# LED_RGBLight_AD_2.net
KiCad netlist of a schematic drawn in Altium Designer
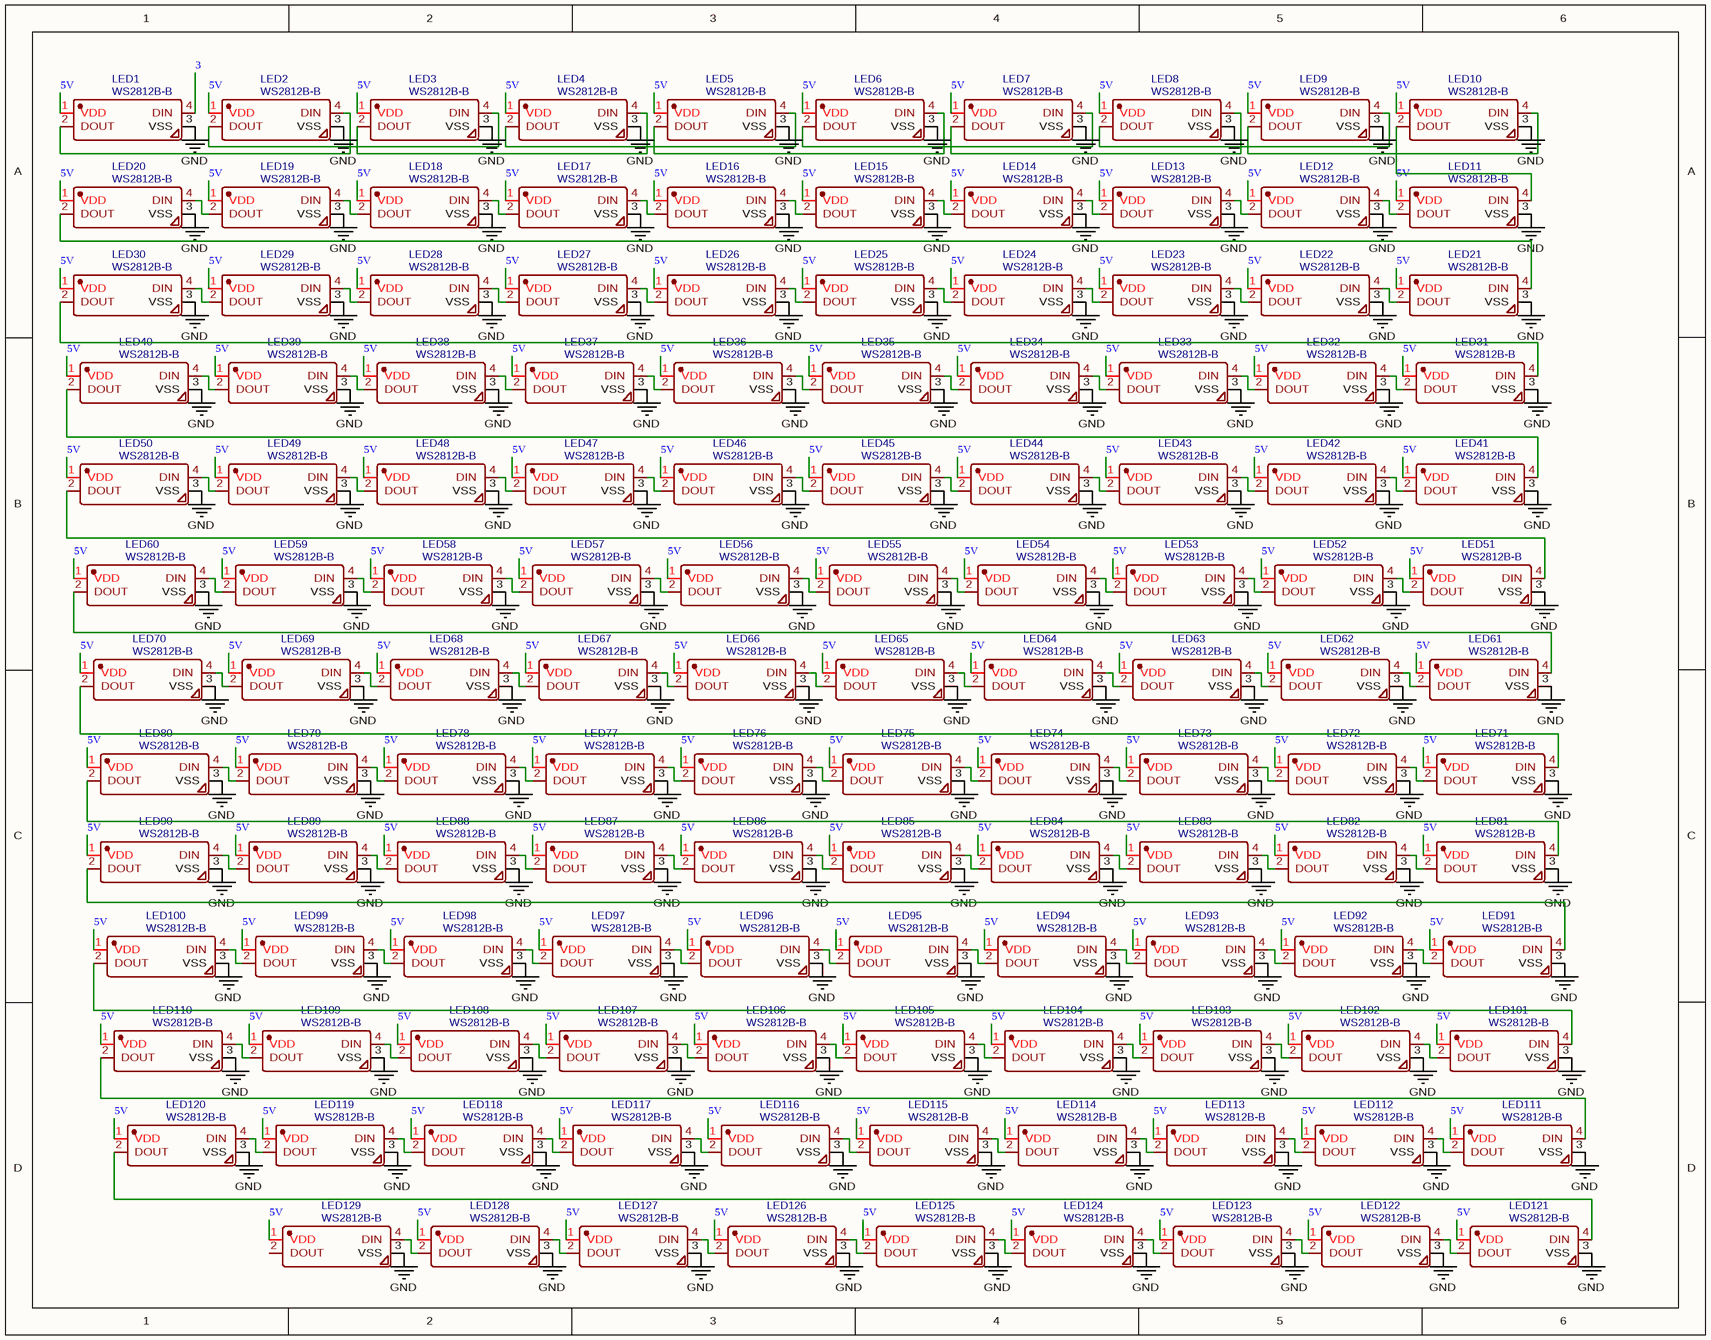
[diagram p0: LED_RGBLight_AD (2).schdoc]

(export (version "E")
  (design (tool "Eeschema 10.0.6"))
  (components
    (comp (ref "LED1")
      (value "WS2812B-B")
      (fields (field (name "BOM_SUPPLIER PART") "C114586") (field (name "CONTRIBUTOR") "LCSC"))
      (libsource (lib "altium-import") (part "root_0_WS2812B-B_"))
    )
    (comp (ref "LED2")
      (value "WS2812B-B")
      (fields (field (name "BOM_SUPPLIER PART") "C114586") (field (name "CONTRIBUTOR") "LCSC"))
      (libsource (lib "altium-import") (part "root_0_WS2812B-B_"))
    )
    (comp (ref "LED3")
      (value "WS2812B-B")
      (fields (field (name "BOM_SUPPLIER PART") "C114586") (field (name "CONTRIBUTOR") "LCSC"))
      (libsource (lib "altium-import") (part "root_0_WS2812B-B_"))
    )
    (comp (ref "LED4")
      (value "WS2812B-B")
      (fields (field (name "BOM_SUPPLIER PART") "C114586") (field (name "CONTRIBUTOR") "LCSC"))
      (libsource (lib "altium-import") (part "root_0_WS2812B-B_"))
    )
    (comp (ref "LED5")
      (value "WS2812B-B")
      (fields (field (name "BOM_SUPPLIER PART") "C114586") (field (name "CONTRIBUTOR") "LCSC"))
      (libsource (lib "altium-import") (part "root_0_WS2812B-B_"))
    )
    (comp (ref "LED6")
      (value "WS2812B-B")
      (fields (field (name "BOM_SUPPLIER PART") "C114586") (field (name "CONTRIBUTOR") "LCSC"))
      (libsource (lib "altium-import") (part "root_0_WS2812B-B_"))
    )
    (comp (ref "LED7")
      (value "WS2812B-B")
      (fields (field (name "BOM_SUPPLIER PART") "C114586") (field (name "CONTRIBUTOR") "LCSC"))
      (libsource (lib "altium-import") (part "root_0_WS2812B-B_"))
    )
    (comp (ref "LED8")
      (value "WS2812B-B")
      (fields (field (name "BOM_SUPPLIER PART") "C114586") (field (name "CONTRIBUTOR") "LCSC"))
      (libsource (lib "altium-import") (part "root_0_WS2812B-B_"))
    )
    (comp (ref "LED9")
      (value "WS2812B-B")
      (fields (field (name "BOM_SUPPLIER PART") "C114586") (field (name "CONTRIBUTOR") "LCSC"))
      (libsource (lib "altium-import") (part "root_0_WS2812B-B_"))
    )
    (comp (ref "LED10")
      (value "WS2812B-B")
      (fields (field (name "BOM_SUPPLIER PART") "C114586") (field (name "CONTRIBUTOR") "LCSC"))
      (libsource (lib "altium-import") (part "root_0_WS2812B-B_"))
    )
    (comp (ref "LED11")
      (value "WS2812B-B")
      (fields (field (name "BOM_SUPPLIER PART") "C114586") (field (name "CONTRIBUTOR") "LCSC"))
      (libsource (lib "altium-import") (part "root_0_WS2812B-B_"))
    )
    (comp (ref "LED12")
      (value "WS2812B-B")
      (fields (field (name "BOM_SUPPLIER PART") "C114586") (field (name "CONTRIBUTOR") "LCSC"))
      (libsource (lib "altium-import") (part "root_0_WS2812B-B_"))
    )
    (comp (ref "LED13")
      (value "WS2812B-B")
      (fields (field (name "BOM_SUPPLIER PART") "C114586") (field (name "CONTRIBUTOR") "LCSC"))
      (libsource (lib "altium-import") (part "root_0_WS2812B-B_"))
    )
    (comp (ref "LED14")
      (value "WS2812B-B")
      (fields (field (name "BOM_SUPPLIER PART") "C114586") (field (name "CONTRIBUTOR") "LCSC"))
      (libsource (lib "altium-import") (part "root_0_WS2812B-B_"))
    )
    (comp (ref "LED15")
      (value "WS2812B-B")
      (fields (field (name "BOM_SUPPLIER PART") "C114586") (field (name "CONTRIBUTOR") "LCSC"))
      (libsource (lib "altium-import") (part "root_0_WS2812B-B_"))
    )
    (comp (ref "LED16")
      (value "WS2812B-B")
      (fields (field (name "BOM_SUPPLIER PART") "C114586") (field (name "CONTRIBUTOR") "LCSC"))
      (libsource (lib "altium-import") (part "root_0_WS2812B-B_"))
    )
    (comp (ref "LED17")
      (value "WS2812B-B")
      (fields (field (name "BOM_SUPPLIER PART") "C114586") (field (name "CONTRIBUTOR") "LCSC"))
      (libsource (lib "altium-import") (part "root_0_WS2812B-B_"))
    )
    (comp (ref "LED18")
      (value "WS2812B-B")
      (fields (field (name "BOM_SUPPLIER PART") "C114586") (field (name "CONTRIBUTOR") "LCSC"))
      (libsource (lib "altium-import") (part "root_0_WS2812B-B_"))
    )
    (comp (ref "LED19")
      (value "WS2812B-B")
      (fields (field (name "BOM_SUPPLIER PART") "C114586") (field (name "CONTRIBUTOR") "LCSC"))
      (libsource (lib "altium-import") (part "root_0_WS2812B-B_"))
    )
    (comp (ref "LED20")
      (value "WS2812B-B")
      (fields (field (name "BOM_SUPPLIER PART") "C114586") (field (name "CONTRIBUTOR") "LCSC"))
      (libsource (lib "altium-import") (part "root_0_WS2812B-B_"))
    )
    (comp (ref "LED21")
      (value "WS2812B-B")
      (fields (field (name "BOM_SUPPLIER PART") "C114586") (field (name "CONTRIBUTOR") "LCSC"))
      (libsource (lib "altium-import") (part "root_0_WS2812B-B_"))
    )
    (comp (ref "LED22")
      (value "WS2812B-B")
      (fields (field (name "BOM_SUPPLIER PART") "C114586") (field (name "CONTRIBUTOR") "LCSC"))
      (libsource (lib "altium-import") (part "root_0_WS2812B-B_"))
    )
    (comp (ref "LED23")
      (value "WS2812B-B")
      (fields (field (name "BOM_SUPPLIER PART") "C114586") (field (name "CONTRIBUTOR") "LCSC"))
      (libsource (lib "altium-import") (part "root_0_WS2812B-B_"))
    )
    (comp (ref "LED24")
      (value "WS2812B-B")
      (fields (field (name "BOM_SUPPLIER PART") "C114586") (field (name "CONTRIBUTOR") "LCSC"))
      (libsource (lib "altium-import") (part "root_0_WS2812B-B_"))
    )
    (comp (ref "LED25")
      (value "WS2812B-B")
      (fields (field (name "BOM_SUPPLIER PART") "C114586") (field (name "CONTRIBUTOR") "LCSC"))
      (libsource (lib "altium-import") (part "root_0_WS2812B-B_"))
    )
    (comp (ref "LED26")
      (value "WS2812B-B")
      (fields (field (name "BOM_SUPPLIER PART") "C114586") (field (name "CONTRIBUTOR") "LCSC"))
      (libsource (lib "altium-import") (part "root_0_WS2812B-B_"))
    )
    (comp (ref "LED27")
      (value "WS2812B-B")
      (fields (field (name "BOM_SUPPLIER PART") "C114586") (field (name "CONTRIBUTOR") "LCSC"))
      (libsource (lib "altium-import") (part "root_0_WS2812B-B_"))
    )
    (comp (ref "LED28")
      (value "WS2812B-B")
      (fields (field (name "BOM_SUPPLIER PART") "C114586") (field (name "CONTRIBUTOR") "LCSC"))
      (libsource (lib "altium-import") (part "root_0_WS2812B-B_"))
    )
    (comp (ref "LED29")
      (value "WS2812B-B")
      (fields (field (name "BOM_SUPPLIER PART") "C114586") (field (name "CONTRIBUTOR") "LCSC"))
      (libsource (lib "altium-import") (part "root_0_WS2812B-B_"))
    )
    (comp (ref "LED30")
      (value "WS2812B-B")
      (fields (field (name "BOM_SUPPLIER PART") "C114586") (field (name "CONTRIBUTOR") "LCSC"))
      (libsource (lib "altium-import") (part "root_0_WS2812B-B_"))
    )
    (comp (ref "LED31")
      (value "WS2812B-B")
      (fields (field (name "BOM_SUPPLIER PART") "C114586") (field (name "CONTRIBUTOR") "LCSC"))
      (libsource (lib "altium-import") (part "root_0_WS2812B-B_"))
    )
    (comp (ref "LED32")
      (value "WS2812B-B")
      (fields (field (name "BOM_SUPPLIER PART") "C114586") (field (name "CONTRIBUTOR") "LCSC"))
      (libsource (lib "altium-import") (part "root_0_WS2812B-B_"))
    )
    (comp (ref "LED33")
      (value "WS2812B-B")
      (fields (field (name "BOM_SUPPLIER PART") "C114586") (field (name "CONTRIBUTOR") "LCSC"))
      (libsource (lib "altium-import") (part "root_0_WS2812B-B_"))
    )
    (comp (ref "LED34")
      (value "WS2812B-B")
      (fields (field (name "BOM_SUPPLIER PART") "C114586") (field (name "CONTRIBUTOR") "LCSC"))
      (libsource (lib "altium-import") (part "root_0_WS2812B-B_"))
    )
    (comp (ref "LED35")
      (value "WS2812B-B")
      (fields (field (name "BOM_SUPPLIER PART") "C114586") (field (name "CONTRIBUTOR") "LCSC"))
      (libsource (lib "altium-import") (part "root_0_WS2812B-B_"))
    )
    (comp (ref "LED36")
      (value "WS2812B-B")
      (fields (field (name "BOM_SUPPLIER PART") "C114586") (field (name "CONTRIBUTOR") "LCSC"))
      (libsource (lib "altium-import") (part "root_0_WS2812B-B_"))
    )
    (comp (ref "LED37")
      (value "WS2812B-B")
      (fields (field (name "BOM_SUPPLIER PART") "C114586") (field (name "CONTRIBUTOR") "LCSC"))
      (libsource (lib "altium-import") (part "root_0_WS2812B-B_"))
    )
    (comp (ref "LED38")
      (value "WS2812B-B")
      (fields (field (name "BOM_SUPPLIER PART") "C114586") (field (name "CONTRIBUTOR") "LCSC"))
      (libsource (lib "altium-import") (part "root_0_WS2812B-B_"))
    )
    (comp (ref "LED39")
      (value "WS2812B-B")
      (fields (field (name "BOM_SUPPLIER PART") "C114586") (field (name "CONTRIBUTOR") "LCSC"))
      (libsource (lib "altium-import") (part "root_0_WS2812B-B_"))
    )
    (comp (ref "LED40")
      (value "WS2812B-B")
      (fields (field (name "BOM_SUPPLIER PART") "C114586") (field (name "CONTRIBUTOR") "LCSC"))
      (libsource (lib "altium-import") (part "root_0_WS2812B-B_"))
    )
    (comp (ref "LED41")
      (value "WS2812B-B")
      (fields (field (name "BOM_SUPPLIER PART") "C114586") (field (name "CONTRIBUTOR") "LCSC"))
      (libsource (lib "altium-import") (part "root_0_WS2812B-B_"))
    )
    (comp (ref "LED42")
      (value "WS2812B-B")
      (fields (field (name "BOM_SUPPLIER PART") "C114586") (field (name "CONTRIBUTOR") "LCSC"))
      (libsource (lib "altium-import") (part "root_0_WS2812B-B_"))
    )
    (comp (ref "LED43")
      (value "WS2812B-B")
      (fields (field (name "BOM_SUPPLIER PART") "C114586") (field (name "CONTRIBUTOR") "LCSC"))
      (libsource (lib "altium-import") (part "root_0_WS2812B-B_"))
    )
    (comp (ref "LED44")
      (value "WS2812B-B")
      (fields (field (name "BOM_SUPPLIER PART") "C114586") (field (name "CONTRIBUTOR") "LCSC"))
      (libsource (lib "altium-import") (part "root_0_WS2812B-B_"))
    )
    (comp (ref "LED45")
      (value "WS2812B-B")
      (fields (field (name "BOM_SUPPLIER PART") "C114586") (field (name "CONTRIBUTOR") "LCSC"))
      (libsource (lib "altium-import") (part "root_0_WS2812B-B_"))
    )
    (comp (ref "LED46")
      (value "WS2812B-B")
      (fields (field (name "BOM_SUPPLIER PART") "C114586") (field (name "CONTRIBUTOR") "LCSC"))
      (libsource (lib "altium-import") (part "root_0_WS2812B-B_"))
    )
    (comp (ref "LED47")
      (value "WS2812B-B")
      (fields (field (name "BOM_SUPPLIER PART") "C114586") (field (name "CONTRIBUTOR") "LCSC"))
      (libsource (lib "altium-import") (part "root_0_WS2812B-B_"))
    )
    (comp (ref "LED48")
      (value "WS2812B-B")
      (fields (field (name "BOM_SUPPLIER PART") "C114586") (field (name "CONTRIBUTOR") "LCSC"))
      (libsource (lib "altium-import") (part "root_0_WS2812B-B_"))
    )
    (comp (ref "LED49")
      (value "WS2812B-B")
      (fields (field (name "BOM_SUPPLIER PART") "C114586") (field (name "CONTRIBUTOR") "LCSC"))
      (libsource (lib "altium-import") (part "root_0_WS2812B-B_"))
    )
    (comp (ref "LED50")
      (value "WS2812B-B")
      (fields (field (name "BOM_SUPPLIER PART") "C114586") (field (name "CONTRIBUTOR") "LCSC"))
      (libsource (lib "altium-import") (part "root_0_WS2812B-B_"))
    )
    (comp (ref "LED51")
      (value "WS2812B-B")
      (fields (field (name "BOM_SUPPLIER PART") "C114586") (field (name "CONTRIBUTOR") "LCSC"))
      (libsource (lib "altium-import") (part "root_0_WS2812B-B_"))
    )
    (comp (ref "LED52")
      (value "WS2812B-B")
      (fields (field (name "BOM_SUPPLIER PART") "C114586") (field (name "CONTRIBUTOR") "LCSC"))
      (libsource (lib "altium-import") (part "root_0_WS2812B-B_"))
    )
    (comp (ref "LED53")
      (value "WS2812B-B")
      (fields (field (name "BOM_SUPPLIER PART") "C114586") (field (name "CONTRIBUTOR") "LCSC"))
      (libsource (lib "altium-import") (part "root_0_WS2812B-B_"))
    )
    (comp (ref "LED54")
      (value "WS2812B-B")
      (fields (field (name "BOM_SUPPLIER PART") "C114586") (field (name "CONTRIBUTOR") "LCSC"))
      (libsource (lib "altium-import") (part "root_0_WS2812B-B_"))
    )
    (comp (ref "LED55")
      (value "WS2812B-B")
      (fields (field (name "BOM_SUPPLIER PART") "C114586") (field (name "CONTRIBUTOR") "LCSC"))
      (libsource (lib "altium-import") (part "root_0_WS2812B-B_"))
    )
    (comp (ref "LED56")
      (value "WS2812B-B")
      (fields (field (name "BOM_SUPPLIER PART") "C114586") (field (name "CONTRIBUTOR") "LCSC"))
      (libsource (lib "altium-import") (part "root_0_WS2812B-B_"))
    )
    (comp (ref "LED57")
      (value "WS2812B-B")
      (fields (field (name "BOM_SUPPLIER PART") "C114586") (field (name "CONTRIBUTOR") "LCSC"))
      (libsource (lib "altium-import") (part "root_0_WS2812B-B_"))
    )
    (comp (ref "LED58")
      (value "WS2812B-B")
      (fields (field (name "BOM_SUPPLIER PART") "C114586") (field (name "CONTRIBUTOR") "LCSC"))
      (libsource (lib "altium-import") (part "root_0_WS2812B-B_"))
    )
    (comp (ref "LED59")
      (value "WS2812B-B")
      (fields (field (name "BOM_SUPPLIER PART") "C114586") (field (name "CONTRIBUTOR") "LCSC"))
      (libsource (lib "altium-import") (part "root_0_WS2812B-B_"))
    )
    (comp (ref "LED60")
      (value "WS2812B-B")
      (fields (field (name "BOM_SUPPLIER PART") "C114586") (field (name "CONTRIBUTOR") "LCSC"))
      (libsource (lib "altium-import") (part "root_0_WS2812B-B_"))
    )
    (comp (ref "LED61")
      (value "WS2812B-B")
      (fields (field (name "BOM_SUPPLIER PART") "C114586") (field (name "CONTRIBUTOR") "LCSC"))
      (libsource (lib "altium-import") (part "root_0_WS2812B-B_"))
    )
    (comp (ref "LED62")
      (value "WS2812B-B")
      (fields (field (name "BOM_SUPPLIER PART") "C114586") (field (name "CONTRIBUTOR") "LCSC"))
      (libsource (lib "altium-import") (part "root_0_WS2812B-B_"))
    )
    (comp (ref "LED63")
      (value "WS2812B-B")
      (fields (field (name "BOM_SUPPLIER PART") "C114586") (field (name "CONTRIBUTOR") "LCSC"))
      (libsource (lib "altium-import") (part "root_0_WS2812B-B_"))
    )
    (comp (ref "LED64")
      (value "WS2812B-B")
      (fields (field (name "BOM_SUPPLIER PART") "C114586") (field (name "CONTRIBUTOR") "LCSC"))
      (libsource (lib "altium-import") (part "root_0_WS2812B-B_"))
    )
    (comp (ref "LED65")
      (value "WS2812B-B")
      (fields (field (name "BOM_SUPPLIER PART") "C114586") (field (name "CONTRIBUTOR") "LCSC"))
      (libsource (lib "altium-import") (part "root_0_WS2812B-B_"))
    )
    (comp (ref "LED66")
      (value "WS2812B-B")
      (fields (field (name "BOM_SUPPLIER PART") "C114586") (field (name "CONTRIBUTOR") "LCSC"))
      (libsource (lib "altium-import") (part "root_0_WS2812B-B_"))
    )
    (comp (ref "LED67")
      (value "WS2812B-B")
      (fields (field (name "BOM_SUPPLIER PART") "C114586") (field (name "CONTRIBUTOR") "LCSC"))
      (libsource (lib "altium-import") (part "root_0_WS2812B-B_"))
    )
    (comp (ref "LED68")
      (value "WS2812B-B")
      (fields (field (name "BOM_SUPPLIER PART") "C114586") (field (name "CONTRIBUTOR") "LCSC"))
      (libsource (lib "altium-import") (part "root_0_WS2812B-B_"))
    )
    (comp (ref "LED69")
      (value "WS2812B-B")
      (fields (field (name "BOM_SUPPLIER PART") "C114586") (field (name "CONTRIBUTOR") "LCSC"))
      (libsource (lib "altium-import") (part "root_0_WS2812B-B_"))
    )
    (comp (ref "LED70")
      (value "WS2812B-B")
      (fields (field (name "BOM_SUPPLIER PART") "C114586") (field (name "CONTRIBUTOR") "LCSC"))
      (libsource (lib "altium-import") (part "root_0_WS2812B-B_"))
    )
    (comp (ref "LED71")
      (value "WS2812B-B")
      (fields (field (name "BOM_SUPPLIER PART") "C114586") (field (name "CONTRIBUTOR") "LCSC"))
      (libsource (lib "altium-import") (part "root_0_WS2812B-B_"))
    )
    (comp (ref "LED72")
      (value "WS2812B-B")
      (fields (field (name "BOM_SUPPLIER PART") "C114586") (field (name "CONTRIBUTOR") "LCSC"))
      (libsource (lib "altium-import") (part "root_0_WS2812B-B_"))
    )
    (comp (ref "LED73")
      (value "WS2812B-B")
      (fields (field (name "BOM_SUPPLIER PART") "C114586") (field (name "CONTRIBUTOR") "LCSC"))
      (libsource (lib "altium-import") (part "root_0_WS2812B-B_"))
    )
    (comp (ref "LED74")
      (value "WS2812B-B")
      (fields (field (name "BOM_SUPPLIER PART") "C114586") (field (name "CONTRIBUTOR") "LCSC"))
      (libsource (lib "altium-import") (part "root_0_WS2812B-B_"))
    )
    (comp (ref "LED75")
      (value "WS2812B-B")
      (fields (field (name "BOM_SUPPLIER PART") "C114586") (field (name "CONTRIBUTOR") "LCSC"))
      (libsource (lib "altium-import") (part "root_0_WS2812B-B_"))
    )
    (comp (ref "LED76")
      (value "WS2812B-B")
      (fields (field (name "BOM_SUPPLIER PART") "C114586") (field (name "CONTRIBUTOR") "LCSC"))
      (libsource (lib "altium-import") (part "root_0_WS2812B-B_"))
    )
    (comp (ref "LED77")
      (value "WS2812B-B")
      (fields (field (name "BOM_SUPPLIER PART") "C114586") (field (name "CONTRIBUTOR") "LCSC"))
      (libsource (lib "altium-import") (part "root_0_WS2812B-B_"))
    )
    (comp (ref "LED78")
      (value "WS2812B-B")
      (fields (field (name "BOM_SUPPLIER PART") "C114586") (field (name "CONTRIBUTOR") "LCSC"))
      (libsource (lib "altium-import") (part "root_0_WS2812B-B_"))
    )
    (comp (ref "LED79")
      (value "WS2812B-B")
      (fields (field (name "BOM_SUPPLIER PART") "C114586") (field (name "CONTRIBUTOR") "LCSC"))
      (libsource (lib "altium-import") (part "root_0_WS2812B-B_"))
    )
    (comp (ref "LED80")
      (value "WS2812B-B")
      (fields (field (name "BOM_SUPPLIER PART") "C114586") (field (name "CONTRIBUTOR") "LCSC"))
      (libsource (lib "altium-import") (part "root_0_WS2812B-B_"))
    )
    (comp (ref "LED81")
      (value "WS2812B-B")
      (fields (field (name "BOM_SUPPLIER PART") "C114586") (field (name "CONTRIBUTOR") "LCSC"))
      (libsource (lib "altium-import") (part "root_0_WS2812B-B_"))
    )
    (comp (ref "LED82")
      (value "WS2812B-B")
      (fields (field (name "BOM_SUPPLIER PART") "C114586") (field (name "CONTRIBUTOR") "LCSC"))
      (libsource (lib "altium-import") (part "root_0_WS2812B-B_"))
    )
    (comp (ref "LED83")
      (value "WS2812B-B")
      (fields (field (name "BOM_SUPPLIER PART") "C114586") (field (name "CONTRIBUTOR") "LCSC"))
      (libsource (lib "altium-import") (part "root_0_WS2812B-B_"))
    )
    (comp (ref "LED84")
      (value "WS2812B-B")
      (fields (field (name "BOM_SUPPLIER PART") "C114586") (field (name "CONTRIBUTOR") "LCSC"))
      (libsource (lib "altium-import") (part "root_0_WS2812B-B_"))
    )
    (comp (ref "LED85")
      (value "WS2812B-B")
      (fields (field (name "BOM_SUPPLIER PART") "C114586") (field (name "CONTRIBUTOR") "LCSC"))
      (libsource (lib "altium-import") (part "root_0_WS2812B-B_"))
    )
    (comp (ref "LED86")
      (value "WS2812B-B")
      (fields (field (name "BOM_SUPPLIER PART") "C114586") (field (name "CONTRIBUTOR") "LCSC"))
      (libsource (lib "altium-import") (part "root_0_WS2812B-B_"))
    )
    (comp (ref "LED87")
      (value "WS2812B-B")
      (fields (field (name "BOM_SUPPLIER PART") "C114586") (field (name "CONTRIBUTOR") "LCSC"))
      (libsource (lib "altium-import") (part "root_0_WS2812B-B_"))
    )
    (comp (ref "LED88")
      (value "WS2812B-B")
      (fields (field (name "BOM_SUPPLIER PART") "C114586") (field (name "CONTRIBUTOR") "LCSC"))
      (libsource (lib "altium-import") (part "root_0_WS2812B-B_"))
    )
    (comp (ref "LED89")
      (value "WS2812B-B")
      (fields (field (name "BOM_SUPPLIER PART") "C114586") (field (name "CONTRIBUTOR") "LCSC"))
      (libsource (lib "altium-import") (part "root_0_WS2812B-B_"))
    )
    (comp (ref "LED90")
      (value "WS2812B-B")
      (fields (field (name "BOM_SUPPLIER PART") "C114586") (field (name "CONTRIBUTOR") "LCSC"))
      (libsource (lib "altium-import") (part "root_0_WS2812B-B_"))
    )
    (comp (ref "LED91")
      (value "WS2812B-B")
      (fields (field (name "BOM_SUPPLIER PART") "C114586") (field (name "CONTRIBUTOR") "LCSC"))
      (libsource (lib "altium-import") (part "root_0_WS2812B-B_"))
    )
    (comp (ref "LED92")
      (value "WS2812B-B")
      (fields (field (name "BOM_SUPPLIER PART") "C114586") (field (name "CONTRIBUTOR") "LCSC"))
      (libsource (lib "altium-import") (part "root_0_WS2812B-B_"))
    )
    (comp (ref "LED93")
      (value "WS2812B-B")
      (fields (field (name "BOM_SUPPLIER PART") "C114586") (field (name "CONTRIBUTOR") "LCSC"))
      (libsource (lib "altium-import") (part "root_0_WS2812B-B_"))
    )
    (comp (ref "LED94")
      (value "WS2812B-B")
      (fields (field (name "BOM_SUPPLIER PART") "C114586") (field (name "CONTRIBUTOR") "LCSC"))
      (libsource (lib "altium-import") (part "root_0_WS2812B-B_"))
    )
    (comp (ref "LED95")
      (value "WS2812B-B")
      (fields (field (name "BOM_SUPPLIER PART") "C114586") (field (name "CONTRIBUTOR") "LCSC"))
      (libsource (lib "altium-import") (part "root_0_WS2812B-B_"))
    )
    (comp (ref "LED96")
      (value "WS2812B-B")
      (fields (field (name "BOM_SUPPLIER PART") "C114586") (field (name "CONTRIBUTOR") "LCSC"))
      (libsource (lib "altium-import") (part "root_0_WS2812B-B_"))
    )
    (comp (ref "LED97")
      (value "WS2812B-B")
      (fields (field (name "BOM_SUPPLIER PART") "C114586") (field (name "CONTRIBUTOR") "LCSC"))
      (libsource (lib "altium-import") (part "root_0_WS2812B-B_"))
    )
    (comp (ref "LED98")
      (value "WS2812B-B")
      (fields (field (name "BOM_SUPPLIER PART") "C114586") (field (name "CONTRIBUTOR") "LCSC"))
      (libsource (lib "altium-import") (part "root_0_WS2812B-B_"))
    )
    (comp (ref "LED99")
      (value "WS2812B-B")
      (fields (field (name "BOM_SUPPLIER PART") "C114586") (field (name "CONTRIBUTOR") "LCSC"))
      (libsource (lib "altium-import") (part "root_0_WS2812B-B_"))
    )
    (comp (ref "LED100")
      (value "WS2812B-B")
      (fields (field (name "BOM_SUPPLIER PART") "C114586") (field (name "CONTRIBUTOR") "LCSC"))
      (libsource (lib "altium-import") (part "root_0_WS2812B-B_"))
    )
    (comp (ref "LED101")
      (value "WS2812B-B")
      (fields (field (name "BOM_SUPPLIER PART") "C114586") (field (name "CONTRIBUTOR") "LCSC"))
      (libsource (lib "altium-import") (part "root_0_WS2812B-B_"))
    )
    (comp (ref "LED102")
      (value "WS2812B-B")
      (fields (field (name "BOM_SUPPLIER PART") "C114586") (field (name "CONTRIBUTOR") "LCSC"))
      (libsource (lib "altium-import") (part "root_0_WS2812B-B_"))
    )
    (comp (ref "LED103")
      (value "WS2812B-B")
      (fields (field (name "BOM_SUPPLIER PART") "C114586") (field (name "CONTRIBUTOR") "LCSC"))
      (libsource (lib "altium-import") (part "root_0_WS2812B-B_"))
    )
    (comp (ref "LED104")
      (value "WS2812B-B")
      (fields (field (name "BOM_SUPPLIER PART") "C114586") (field (name "CONTRIBUTOR") "LCSC"))
      (libsource (lib "altium-import") (part "root_0_WS2812B-B_"))
    )
    (comp (ref "LED105")
      (value "WS2812B-B")
      (fields (field (name "BOM_SUPPLIER PART") "C114586") (field (name "CONTRIBUTOR") "LCSC"))
      (libsource (lib "altium-import") (part "root_0_WS2812B-B_"))
    )
    (comp (ref "LED106")
      (value "WS2812B-B")
      (fields (field (name "BOM_SUPPLIER PART") "C114586") (field (name "CONTRIBUTOR") "LCSC"))
      (libsource (lib "altium-import") (part "root_0_WS2812B-B_"))
    )
    (comp (ref "LED107")
      (value "WS2812B-B")
      (fields (field (name "BOM_SUPPLIER PART") "C114586") (field (name "CONTRIBUTOR") "LCSC"))
      (libsource (lib "altium-import") (part "root_0_WS2812B-B_"))
    )
    (comp (ref "LED108")
      (value "WS2812B-B")
      (fields (field (name "BOM_SUPPLIER PART") "C114586") (field (name "CONTRIBUTOR") "LCSC"))
      (libsource (lib "altium-import") (part "root_0_WS2812B-B_"))
    )
    (comp (ref "LED109")
      (value "WS2812B-B")
      (fields (field (name "BOM_SUPPLIER PART") "C114586") (field (name "CONTRIBUTOR") "LCSC"))
      (libsource (lib "altium-import") (part "root_0_WS2812B-B_"))
    )
    (comp (ref "LED110")
      (value "WS2812B-B")
      (fields (field (name "BOM_SUPPLIER PART") "C114586") (field (name "CONTRIBUTOR") "LCSC"))
      (libsource (lib "altium-import") (part "root_0_WS2812B-B_"))
    )
    (comp (ref "LED111")
      (value "WS2812B-B")
      (fields (field (name "BOM_SUPPLIER PART") "C114586") (field (name "CONTRIBUTOR") "LCSC"))
      (libsource (lib "altium-import") (part "root_0_WS2812B-B_"))
    )
    (comp (ref "LED112")
      (value "WS2812B-B")
      (fields (field (name "BOM_SUPPLIER PART") "C114586") (field (name "CONTRIBUTOR") "LCSC"))
      (libsource (lib "altium-import") (part "root_0_WS2812B-B_"))
    )
    (comp (ref "LED113")
      (value "WS2812B-B")
      (fields (field (name "BOM_SUPPLIER PART") "C114586") (field (name "CONTRIBUTOR") "LCSC"))
      (libsource (lib "altium-import") (part "root_0_WS2812B-B_"))
    )
    (comp (ref "LED114")
      (value "WS2812B-B")
      (fields (field (name "BOM_SUPPLIER PART") "C114586") (field (name "CONTRIBUTOR") "LCSC"))
      (libsource (lib "altium-import") (part "root_0_WS2812B-B_"))
    )
    (comp (ref "LED115")
      (value "WS2812B-B")
      (fields (field (name "BOM_SUPPLIER PART") "C114586") (field (name "CONTRIBUTOR") "LCSC"))
      (libsource (lib "altium-import") (part "root_0_WS2812B-B_"))
    )
    (comp (ref "LED116")
      (value "WS2812B-B")
      (fields (field (name "BOM_SUPPLIER PART") "C114586") (field (name "CONTRIBUTOR") "LCSC"))
      (libsource (lib "altium-import") (part "root_0_WS2812B-B_"))
    )
    (comp (ref "LED117")
      (value "WS2812B-B")
      (fields (field (name "BOM_SUPPLIER PART") "C114586") (field (name "CONTRIBUTOR") "LCSC"))
      (libsource (lib "altium-import") (part "root_0_WS2812B-B_"))
    )
    (comp (ref "LED118")
      (value "WS2812B-B")
      (fields (field (name "BOM_SUPPLIER PART") "C114586") (field (name "CONTRIBUTOR") "LCSC"))
      (libsource (lib "altium-import") (part "root_0_WS2812B-B_"))
    )
    (comp (ref "LED119")
      (value "WS2812B-B")
      (fields (field (name "BOM_SUPPLIER PART") "C114586") (field (name "CONTRIBUTOR") "LCSC"))
      (libsource (lib "altium-import") (part "root_0_WS2812B-B_"))
    )
    (comp (ref "LED120")
      (value "WS2812B-B")
      (fields (field (name "BOM_SUPPLIER PART") "C114586") (field (name "CONTRIBUTOR") "LCSC"))
      (libsource (lib "altium-import") (part "root_0_WS2812B-B_"))
    )
    (comp (ref "LED121")
      (value "WS2812B-B")
      (fields (field (name "BOM_SUPPLIER PART") "C114586") (field (name "CONTRIBUTOR") "LCSC"))
      (libsource (lib "altium-import") (part "root_0_WS2812B-B_"))
    )
    (comp (ref "LED122")
      (value "WS2812B-B")
      (fields (field (name "BOM_SUPPLIER PART") "C114586") (field (name "CONTRIBUTOR") "LCSC"))
      (libsource (lib "altium-import") (part "root_0_WS2812B-B_"))
    )
    (comp (ref "LED123")
      (value "WS2812B-B")
      (fields (field (name "BOM_SUPPLIER PART") "C114586") (field (name "CONTRIBUTOR") "LCSC"))
      (libsource (lib "altium-import") (part "root_0_WS2812B-B_"))
    )
    (comp (ref "LED124")
      (value "WS2812B-B")
      (fields (field (name "BOM_SUPPLIER PART") "C114586") (field (name "CONTRIBUTOR") "LCSC"))
      (libsource (lib "altium-import") (part "root_0_WS2812B-B_"))
    )
    (comp (ref "LED125")
      (value "WS2812B-B")
      (fields (field (name "BOM_SUPPLIER PART") "C114586") (field (name "CONTRIBUTOR") "LCSC"))
      (libsource (lib "altium-import") (part "root_0_WS2812B-B_"))
    )
    (comp (ref "LED126")
      (value "WS2812B-B")
      (fields (field (name "BOM_SUPPLIER PART") "C114586") (field (name "CONTRIBUTOR") "LCSC"))
      (libsource (lib "altium-import") (part "root_0_WS2812B-B_"))
    )
    (comp (ref "LED127")
      (value "WS2812B-B")
      (fields (field (name "BOM_SUPPLIER PART") "C114586") (field (name "CONTRIBUTOR") "LCSC"))
      (libsource (lib "altium-import") (part "root_0_WS2812B-B_"))
    )
    (comp (ref "LED128")
      (value "WS2812B-B")
      (fields (field (name "BOM_SUPPLIER PART") "C114586") (field (name "CONTRIBUTOR") "LCSC"))
      (libsource (lib "altium-import") (part "root_0_WS2812B-B_"))
    )
    (comp (ref "LED129")
      (value "WS2812B-B")
      (fields (field (name "BOM_SUPPLIER PART") "C114586") (field (name "CONTRIBUTOR") "LCSC"))
      (libsource (lib "altium-import") (part "root_0_WS2812B-B_"))
    )
  )
  (nets
    (net (code "1") (name "/3") (class "Default")
      (node (ref "LED1") (pin "4") (pinfunction "DIN_4") (pintype "passive"))
    )
    (net (code "2") (name "/5V") (class "Default")
      (node (ref "LED1") (pin "1") (pinfunction "VDD_1") (pintype "passive"))
      (node (ref "LED10") (pin "1") (pinfunction "VDD_1") (pintype "passive"))
      (node (ref "LED100") (pin "1") (pinfunction "VDD_1") (pintype "passive"))
      (node (ref "LED101") (pin "1") (pinfunction "VDD_1") (pintype "passive"))
      (node (ref "LED102") (pin "1") (pinfunction "VDD_1") (pintype "passive"))
      (node (ref "LED103") (pin "1") (pinfunction "VDD_1") (pintype "passive"))
      (node (ref "LED104") (pin "1") (pinfunction "VDD_1") (pintype "passive"))
      (node (ref "LED105") (pin "1") (pinfunction "VDD_1") (pintype "passive"))
      (node (ref "LED106") (pin "1") (pinfunction "VDD_1") (pintype "passive"))
      (node (ref "LED107") (pin "1") (pinfunction "VDD_1") (pintype "passive"))
      (node (ref "LED108") (pin "1") (pinfunction "VDD_1") (pintype "passive"))
      (node (ref "LED109") (pin "1") (pinfunction "VDD_1") (pintype "passive"))
      (node (ref "LED11") (pin "1") (pinfunction "VDD_1") (pintype "passive"))
      (node (ref "LED110") (pin "1") (pinfunction "VDD_1") (pintype "passive"))
      (node (ref "LED111") (pin "1") (pinfunction "VDD_1") (pintype "passive"))
      (node (ref "LED112") (pin "1") (pinfunction "VDD_1") (pintype "passive"))
      (node (ref "LED113") (pin "1") (pinfunction "VDD_1") (pintype "passive"))
      (node (ref "LED114") (pin "1") (pinfunction "VDD_1") (pintype "passive"))
      (node (ref "LED115") (pin "1") (pinfunction "VDD_1") (pintype "passive"))
      (node (ref "LED116") (pin "1") (pinfunction "VDD_1") (pintype "passive"))
      (node (ref "LED117") (pin "1") (pinfunction "VDD_1") (pintype "passive"))
      (node (ref "LED118") (pin "1") (pinfunction "VDD_1") (pintype "passive"))
      (node (ref "LED119") (pin "1") (pinfunction "VDD_1") (pintype "passive"))
      (node (ref "LED12") (pin "1") (pinfunction "VDD_1") (pintype "passive"))
      (node (ref "LED120") (pin "1") (pinfunction "VDD_1") (pintype "passive"))
      (node (ref "LED121") (pin "1") (pinfunction "VDD_1") (pintype "passive"))
      (node (ref "LED122") (pin "1") (pinfunction "VDD_1") (pintype "passive"))
      (node (ref "LED123") (pin "1") (pinfunction "VDD_1") (pintype "passive"))
      (node (ref "LED124") (pin "1") (pinfunction "VDD_1") (pintype "passive"))
      (node (ref "LED125") (pin "1") (pinfunction "VDD_1") (pintype "passive"))
      (node (ref "LED126") (pin "1") (pinfunction "VDD_1") (pintype "passive"))
      (node (ref "LED127") (pin "1") (pinfunction "VDD_1") (pintype "passive"))
      (node (ref "LED128") (pin "1") (pinfunction "VDD_1") (pintype "passive"))
      (node (ref "LED129") (pin "1") (pinfunction "VDD_1") (pintype "passive"))
      (node (ref "LED13") (pin "1") (pinfunction "VDD_1") (pintype "passive"))
      (node (ref "LED14") (pin "1") (pinfunction "VDD_1") (pintype "passive"))
      (node (ref "LED15") (pin "1") (pinfunction "VDD_1") (pintype "passive"))
      (node (ref "LED16") (pin "1") (pinfunction "VDD_1") (pintype "passive"))
      (node (ref "LED17") (pin "1") (pinfunction "VDD_1") (pintype "passive"))
      (node (ref "LED18") (pin "1") (pinfunction "VDD_1") (pintype "passive"))
      (node (ref "LED19") (pin "1") (pinfunction "VDD_1") (pintype "passive"))
      (node (ref "LED2") (pin "1") (pinfunction "VDD_1") (pintype "passive"))
      (node (ref "LED20") (pin "1") (pinfunction "VDD_1") (pintype "passive"))
      (node (ref "LED21") (pin "1") (pinfunction "VDD_1") (pintype "passive"))
      (node (ref "LED22") (pin "1") (pinfunction "VDD_1") (pintype "passive"))
      (node (ref "LED23") (pin "1") (pinfunction "VDD_1") (pintype "passive"))
      (node (ref "LED24") (pin "1") (pinfunction "VDD_1") (pintype "passive"))
      (node (ref "LED25") (pin "1") (pinfunction "VDD_1") (pintype "passive"))
      (node (ref "LED26") (pin "1") (pinfunction "VDD_1") (pintype "passive"))
      (node (ref "LED27") (pin "1") (pinfunction "VDD_1") (pintype "passive"))
      (node (ref "LED28") (pin "1") (pinfunction "VDD_1") (pintype "passive"))
      (node (ref "LED29") (pin "1") (pinfunction "VDD_1") (pintype "passive"))
      (node (ref "LED3") (pin "1") (pinfunction "VDD_1") (pintype "passive"))
      (node (ref "LED30") (pin "1") (pinfunction "VDD_1") (pintype "passive"))
      (node (ref "LED31") (pin "1") (pinfunction "VDD_1") (pintype "passive"))
      (node (ref "LED32") (pin "1") (pinfunction "VDD_1") (pintype "passive"))
      (node (ref "LED33") (pin "1") (pinfunction "VDD_1") (pintype "passive"))
      (node (ref "LED34") (pin "1") (pinfunction "VDD_1") (pintype "passive"))
      (node (ref "LED35") (pin "1") (pinfunction "VDD_1") (pintype "passive"))
      (node (ref "LED36") (pin "1") (pinfunction "VDD_1") (pintype "passive"))
      (node (ref "LED37") (pin "1") (pinfunction "VDD_1") (pintype "passive"))
      (node (ref "LED38") (pin "1") (pinfunction "VDD_1") (pintype "passive"))
      (node (ref "LED39") (pin "1") (pinfunction "VDD_1") (pintype "passive"))
      (node (ref "LED4") (pin "1") (pinfunction "VDD_1") (pintype "passive"))
      (node (ref "LED40") (pin "1") (pinfunction "VDD_1") (pintype "passive"))
      (node (ref "LED41") (pin "1") (pinfunction "VDD_1") (pintype "passive"))
      (node (ref "LED42") (pin "1") (pinfunction "VDD_1") (pintype "passive"))
      (node (ref "LED43") (pin "1") (pinfunction "VDD_1") (pintype "passive"))
      (node (ref "LED44") (pin "1") (pinfunction "VDD_1") (pintype "passive"))
      (node (ref "LED45") (pin "1") (pinfunction "VDD_1") (pintype "passive"))
      (node (ref "LED46") (pin "1") (pinfunction "VDD_1") (pintype "passive"))
      (node (ref "LED47") (pin "1") (pinfunction "VDD_1") (pintype "passive"))
      (node (ref "LED48") (pin "1") (pinfunction "VDD_1") (pintype "passive"))
      (node (ref "LED49") (pin "1") (pinfunction "VDD_1") (pintype "passive"))
      (node (ref "LED5") (pin "1") (pinfunction "VDD_1") (pintype "passive"))
      (node (ref "LED50") (pin "1") (pinfunction "VDD_1") (pintype "passive"))
      (node (ref "LED51") (pin "1") (pinfunction "VDD_1") (pintype "passive"))
      (node (ref "LED52") (pin "1") (pinfunction "VDD_1") (pintype "passive"))
      (node (ref "LED53") (pin "1") (pinfunction "VDD_1") (pintype "passive"))
      (node (ref "LED54") (pin "1") (pinfunction "VDD_1") (pintype "passive"))
      (node (ref "LED55") (pin "1") (pinfunction "VDD_1") (pintype "passive"))
      (node (ref "LED56") (pin "1") (pinfunction "VDD_1") (pintype "passive"))
      (node (ref "LED57") (pin "1") (pinfunction "VDD_1") (pintype "passive"))
      (node (ref "LED58") (pin "1") (pinfunction "VDD_1") (pintype "passive"))
      (node (ref "LED59") (pin "1") (pinfunction "VDD_1") (pintype "passive"))
      (node (ref "LED6") (pin "1") (pinfunction "VDD_1") (pintype "passive"))
      (node (ref "LED60") (pin "1") (pinfunction "VDD_1") (pintype "passive"))
      (node (ref "LED61") (pin "1") (pinfunction "VDD_1") (pintype "passive"))
      (node (ref "LED62") (pin "1") (pinfunction "VDD_1") (pintype "passive"))
      (node (ref "LED63") (pin "1") (pinfunction "VDD_1") (pintype "passive"))
      (node (ref "LED64") (pin "1") (pinfunction "VDD_1") (pintype "passive"))
      (node (ref "LED65") (pin "1") (pinfunction "VDD_1") (pintype "passive"))
      (node (ref "LED66") (pin "1") (pinfunction "VDD_1") (pintype "passive"))
      (node (ref "LED67") (pin "1") (pinfunction "VDD_1") (pintype "passive"))
      (node (ref "LED68") (pin "1") (pinfunction "VDD_1") (pintype "passive"))
      (node (ref "LED69") (pin "1") (pinfunction "VDD_1") (pintype "passive"))
      (node (ref "LED7") (pin "1") (pinfunction "VDD_1") (pintype "passive"))
      (node (ref "LED70") (pin "1") (pinfunction "VDD_1") (pintype "passive"))
      (node (ref "LED71") (pin "1") (pinfunction "VDD_1") (pintype "passive"))
      (node (ref "LED72") (pin "1") (pinfunction "VDD_1") (pintype "passive"))
      (node (ref "LED73") (pin "1") (pinfunction "VDD_1") (pintype "passive"))
      (node (ref "LED74") (pin "1") (pinfunction "VDD_1") (pintype "passive"))
      (node (ref "LED75") (pin "1") (pinfunction "VDD_1") (pintype "passive"))
      (node (ref "LED76") (pin "1") (pinfunction "VDD_1") (pintype "passive"))
      (node (ref "LED77") (pin "1") (pinfunction "VDD_1") (pintype "passive"))
      (node (ref "LED78") (pin "1") (pinfunction "VDD_1") (pintype "passive"))
      (node (ref "LED79") (pin "1") (pinfunction "VDD_1") (pintype "passive"))
      (node (ref "LED8") (pin "1") (pinfunction "VDD_1") (pintype "passive"))
      (node (ref "LED80") (pin "1") (pinfunction "VDD_1") (pintype "passive"))
      (node (ref "LED81") (pin "1") (pinfunction "VDD_1") (pintype "passive"))
      (node (ref "LED82") (pin "1") (pinfunction "VDD_1") (pintype "passive"))
      (node (ref "LED83") (pin "1") (pinfunction "VDD_1") (pintype "passive"))
      (node (ref "LED84") (pin "1") (pinfunction "VDD_1") (pintype "passive"))
      (node (ref "LED85") (pin "1") (pinfunction "VDD_1") (pintype "passive"))
      (node (ref "LED86") (pin "1") (pinfunction "VDD_1") (pintype "passive"))
      (node (ref "LED87") (pin "1") (pinfunction "VDD_1") (pintype "passive"))
      (node (ref "LED88") (pin "1") (pinfunction "VDD_1") (pintype "passive"))
      (node (ref "LED89") (pin "1") (pinfunction "VDD_1") (pintype "passive"))
      (node (ref "LED9") (pin "1") (pinfunction "VDD_1") (pintype "passive"))
      (node (ref "LED90") (pin "1") (pinfunction "VDD_1") (pintype "passive"))
      (node (ref "LED91") (pin "1") (pinfunction "VDD_1") (pintype "passive"))
      (node (ref "LED92") (pin "1") (pinfunction "VDD_1") (pintype "passive"))
      (node (ref "LED93") (pin "1") (pinfunction "VDD_1") (pintype "passive"))
      (node (ref "LED94") (pin "1") (pinfunction "VDD_1") (pintype "passive"))
      (node (ref "LED95") (pin "1") (pinfunction "VDD_1") (pintype "passive"))
      (node (ref "LED96") (pin "1") (pinfunction "VDD_1") (pintype "passive"))
      (node (ref "LED97") (pin "1") (pinfunction "VDD_1") (pintype "passive"))
      (node (ref "LED98") (pin "1") (pinfunction "VDD_1") (pintype "passive"))
      (node (ref "LED99") (pin "1") (pinfunction "VDD_1") (pintype "passive"))
    )
    (net (code "3") (name "GND") (class "Default")
      (node (ref "LED1") (pin "3") (pinfunction "VSS_3") (pintype "passive"))
      (node (ref "LED10") (pin "3") (pinfunction "VSS_3") (pintype "passive"))
      (node (ref "LED100") (pin "3") (pinfunction "VSS_3") (pintype "passive"))
      (node (ref "LED101") (pin "3") (pinfunction "VSS_3") (pintype "passive"))
      (node (ref "LED102") (pin "3") (pinfunction "VSS_3") (pintype "passive"))
      (node (ref "LED103") (pin "3") (pinfunction "VSS_3") (pintype "passive"))
      (node (ref "LED104") (pin "3") (pinfunction "VSS_3") (pintype "passive"))
      (node (ref "LED105") (pin "3") (pinfunction "VSS_3") (pintype "passive"))
      (node (ref "LED106") (pin "3") (pinfunction "VSS_3") (pintype "passive"))
      (node (ref "LED107") (pin "3") (pinfunction "VSS_3") (pintype "passive"))
      (node (ref "LED108") (pin "3") (pinfunction "VSS_3") (pintype "passive"))
      (node (ref "LED109") (pin "3") (pinfunction "VSS_3") (pintype "passive"))
      (node (ref "LED11") (pin "3") (pinfunction "VSS_3") (pintype "passive"))
      (node (ref "LED110") (pin "3") (pinfunction "VSS_3") (pintype "passive"))
      (node (ref "LED111") (pin "3") (pinfunction "VSS_3") (pintype "passive"))
      (node (ref "LED112") (pin "3") (pinfunction "VSS_3") (pintype "passive"))
      (node (ref "LED113") (pin "3") (pinfunction "VSS_3") (pintype "passive"))
      (node (ref "LED114") (pin "3") (pinfunction "VSS_3") (pintype "passive"))
      (node (ref "LED115") (pin "3") (pinfunction "VSS_3") (pintype "passive"))
      (node (ref "LED116") (pin "3") (pinfunction "VSS_3") (pintype "passive"))
      (node (ref "LED117") (pin "3") (pinfunction "VSS_3") (pintype "passive"))
      (node (ref "LED118") (pin "3") (pinfunction "VSS_3") (pintype "passive"))
      (node (ref "LED119") (pin "3") (pinfunction "VSS_3") (pintype "passive"))
      (node (ref "LED12") (pin "3") (pinfunction "VSS_3") (pintype "passive"))
      (node (ref "LED120") (pin "3") (pinfunction "VSS_3") (pintype "passive"))
      (node (ref "LED121") (pin "3") (pinfunction "VSS_3") (pintype "passive"))
      (node (ref "LED122") (pin "3") (pinfunction "VSS_3") (pintype "passive"))
      (node (ref "LED123") (pin "3") (pinfunction "VSS_3") (pintype "passive"))
      (node (ref "LED124") (pin "3") (pinfunction "VSS_3") (pintype "passive"))
      (node (ref "LED125") (pin "3") (pinfunction "VSS_3") (pintype "passive"))
      (node (ref "LED126") (pin "3") (pinfunction "VSS_3") (pintype "passive"))
      (node (ref "LED127") (pin "3") (pinfunction "VSS_3") (pintype "passive"))
      (node (ref "LED128") (pin "3") (pinfunction "VSS_3") (pintype "passive"))
      (node (ref "LED129") (pin "3") (pinfunction "VSS_3") (pintype "passive"))
      (node (ref "LED13") (pin "3") (pinfunction "VSS_3") (pintype "passive"))
      (node (ref "LED14") (pin "3") (pinfunction "VSS_3") (pintype "passive"))
      (node (ref "LED15") (pin "3") (pinfunction "VSS_3") (pintype "passive"))
      (node (ref "LED16") (pin "3") (pinfunction "VSS_3") (pintype "passive"))
      (node (ref "LED17") (pin "3") (pinfunction "VSS_3") (pintype "passive"))
      (node (ref "LED18") (pin "3") (pinfunction "VSS_3") (pintype "passive"))
      (node (ref "LED19") (pin "3") (pinfunction "VSS_3") (pintype "passive"))
      (node (ref "LED2") (pin "3") (pinfunction "VSS_3") (pintype "passive"))
      (node (ref "LED20") (pin "3") (pinfunction "VSS_3") (pintype "passive"))
      (node (ref "LED21") (pin "3") (pinfunction "VSS_3") (pintype "passive"))
      (node (ref "LED22") (pin "3") (pinfunction "VSS_3") (pintype "passive"))
      (node (ref "LED23") (pin "3") (pinfunction "VSS_3") (pintype "passive"))
      (node (ref "LED24") (pin "3") (pinfunction "VSS_3") (pintype "passive"))
      (node (ref "LED25") (pin "3") (pinfunction "VSS_3") (pintype "passive"))
      (node (ref "LED26") (pin "3") (pinfunction "VSS_3") (pintype "passive"))
      (node (ref "LED27") (pin "3") (pinfunction "VSS_3") (pintype "passive"))
      (node (ref "LED28") (pin "3") (pinfunction "VSS_3") (pintype "passive"))
      (node (ref "LED29") (pin "3") (pinfunction "VSS_3") (pintype "passive"))
      (node (ref "LED3") (pin "3") (pinfunction "VSS_3") (pintype "passive"))
      (node (ref "LED30") (pin "3") (pinfunction "VSS_3") (pintype "passive"))
      (node (ref "LED31") (pin "3") (pinfunction "VSS_3") (pintype "passive"))
      (node (ref "LED32") (pin "3") (pinfunction "VSS_3") (pintype "passive"))
      (node (ref "LED33") (pin "3") (pinfunction "VSS_3") (pintype "passive"))
      (node (ref "LED34") (pin "3") (pinfunction "VSS_3") (pintype "passive"))
      (node (ref "LED35") (pin "3") (pinfunction "VSS_3") (pintype "passive"))
      (node (ref "LED36") (pin "3") (pinfunction "VSS_3") (pintype "passive"))
      (node (ref "LED37") (pin "3") (pinfunction "VSS_3") (pintype "passive"))
      (node (ref "LED38") (pin "3") (pinfunction "VSS_3") (pintype "passive"))
      (node (ref "LED39") (pin "3") (pinfunction "VSS_3") (pintype "passive"))
      (node (ref "LED4") (pin "3") (pinfunction "VSS_3") (pintype "passive"))
      (node (ref "LED40") (pin "3") (pinfunction "VSS_3") (pintype "passive"))
      (node (ref "LED41") (pin "3") (pinfunction "VSS_3") (pintype "passive"))
      (node (ref "LED42") (pin "3") (pinfunction "VSS_3") (pintype "passive"))
      (node (ref "LED43") (pin "3") (pinfunction "VSS_3") (pintype "passive"))
      (node (ref "LED44") (pin "3") (pinfunction "VSS_3") (pintype "passive"))
      (node (ref "LED45") (pin "3") (pinfunction "VSS_3") (pintype "passive"))
      (node (ref "LED46") (pin "3") (pinfunction "VSS_3") (pintype "passive"))
      (node (ref "LED47") (pin "3") (pinfunction "VSS_3") (pintype "passive"))
      (node (ref "LED48") (pin "3") (pinfunction "VSS_3") (pintype "passive"))
      (node (ref "LED49") (pin "3") (pinfunction "VSS_3") (pintype "passive"))
      (node (ref "LED5") (pin "3") (pinfunction "VSS_3") (pintype "passive"))
      (node (ref "LED50") (pin "3") (pinfunction "VSS_3") (pintype "passive"))
      (node (ref "LED51") (pin "3") (pinfunction "VSS_3") (pintype "passive"))
      (node (ref "LED52") (pin "3") (pinfunction "VSS_3") (pintype "passive"))
      (node (ref "LED53") (pin "3") (pinfunction "VSS_3") (pintype "passive"))
      (node (ref "LED54") (pin "3") (pinfunction "VSS_3") (pintype "passive"))
      (node (ref "LED55") (pin "3") (pinfunction "VSS_3") (pintype "passive"))
      (node (ref "LED56") (pin "3") (pinfunction "VSS_3") (pintype "passive"))
      (node (ref "LED57") (pin "3") (pinfunction "VSS_3") (pintype "passive"))
      (node (ref "LED58") (pin "3") (pinfunction "VSS_3") (pintype "passive"))
      (node (ref "LED59") (pin "3") (pinfunction "VSS_3") (pintype "passive"))
      (node (ref "LED6") (pin "3") (pinfunction "VSS_3") (pintype "passive"))
      (node (ref "LED60") (pin "3") (pinfunction "VSS_3") (pintype "passive"))
      (node (ref "LED61") (pin "3") (pinfunction "VSS_3") (pintype "passive"))
      (node (ref "LED62") (pin "3") (pinfunction "VSS_3") (pintype "passive"))
      (node (ref "LED63") (pin "3") (pinfunction "VSS_3") (pintype "passive"))
      (node (ref "LED64") (pin "3") (pinfunction "VSS_3") (pintype "passive"))
      (node (ref "LED65") (pin "3") (pinfunction "VSS_3") (pintype "passive"))
      (node (ref "LED66") (pin "3") (pinfunction "VSS_3") (pintype "passive"))
      (node (ref "LED67") (pin "3") (pinfunction "VSS_3") (pintype "passive"))
      (node (ref "LED68") (pin "3") (pinfunction "VSS_3") (pintype "passive"))
      (node (ref "LED69") (pin "3") (pinfunction "VSS_3") (pintype "passive"))
      (node (ref "LED7") (pin "3") (pinfunction "VSS_3") (pintype "passive"))
      (node (ref "LED70") (pin "3") (pinfunction "VSS_3") (pintype "passive"))
      (node (ref "LED71") (pin "3") (pinfunction "VSS_3") (pintype "passive"))
      (node (ref "LED72") (pin "3") (pinfunction "VSS_3") (pintype "passive"))
      (node (ref "LED73") (pin "3") (pinfunction "VSS_3") (pintype "passive"))
      (node (ref "LED74") (pin "3") (pinfunction "VSS_3") (pintype "passive"))
      (node (ref "LED75") (pin "3") (pinfunction "VSS_3") (pintype "passive"))
      (node (ref "LED76") (pin "3") (pinfunction "VSS_3") (pintype "passive"))
      (node (ref "LED77") (pin "3") (pinfunction "VSS_3") (pintype "passive"))
      (node (ref "LED78") (pin "3") (pinfunction "VSS_3") (pintype "passive"))
      (node (ref "LED79") (pin "3") (pinfunction "VSS_3") (pintype "passive"))
      (node (ref "LED8") (pin "3") (pinfunction "VSS_3") (pintype "passive"))
      (node (ref "LED80") (pin "3") (pinfunction "VSS_3") (pintype "passive"))
      (node (ref "LED81") (pin "3") (pinfunction "VSS_3") (pintype "passive"))
      (node (ref "LED82") (pin "3") (pinfunction "VSS_3") (pintype "passive"))
      (node (ref "LED83") (pin "3") (pinfunction "VSS_3") (pintype "passive"))
      (node (ref "LED84") (pin "3") (pinfunction "VSS_3") (pintype "passive"))
      (node (ref "LED85") (pin "3") (pinfunction "VSS_3") (pintype "passive"))
      (node (ref "LED86") (pin "3") (pinfunction "VSS_3") (pintype "passive"))
      (node (ref "LED87") (pin "3") (pinfunction "VSS_3") (pintype "passive"))
      (node (ref "LED88") (pin "3") (pinfunction "VSS_3") (pintype "passive"))
      (node (ref "LED89") (pin "3") (pinfunction "VSS_3") (pintype "passive"))
      (node (ref "LED9") (pin "3") (pinfunction "VSS_3") (pintype "passive"))
      (node (ref "LED90") (pin "3") (pinfunction "VSS_3") (pintype "passive"))
      (node (ref "LED91") (pin "3") (pinfunction "VSS_3") (pintype "passive"))
      (node (ref "LED92") (pin "3") (pinfunction "VSS_3") (pintype "passive"))
      (node (ref "LED93") (pin "3") (pinfunction "VSS_3") (pintype "passive"))
      (node (ref "LED94") (pin "3") (pinfunction "VSS_3") (pintype "passive"))
      (node (ref "LED95") (pin "3") (pinfunction "VSS_3") (pintype "passive"))
      (node (ref "LED96") (pin "3") (pinfunction "VSS_3") (pintype "passive"))
      (node (ref "LED97") (pin "3") (pinfunction "VSS_3") (pintype "passive"))
      (node (ref "LED98") (pin "3") (pinfunction "VSS_3") (pintype "passive"))
      (node (ref "LED99") (pin "3") (pinfunction "VSS_3") (pintype "passive"))
    )
    (net (code "4") (name "Net-(LED1-DOUT)") (class "Default")
      (node (ref "LED1") (pin "2") (pinfunction "DOUT_2") (pintype "passive"))
      (node (ref "LED2") (pin "4") (pinfunction "DIN_4") (pintype "passive"))
    )
    (net (code "5") (name "Net-(LED2-DOUT)") (class "Default")
      (node (ref "LED2") (pin "2") (pinfunction "DOUT_2") (pintype "passive"))
      (node (ref "LED3") (pin "4") (pinfunction "DIN_4") (pintype "passive"))
    )
    (net (code "6") (name "Net-(LED3-DOUT)") (class "Default")
      (node (ref "LED3") (pin "2") (pinfunction "DOUT_2") (pintype "passive"))
      (node (ref "LED4") (pin "4") (pinfunction "DIN_4") (pintype "passive"))
    )
    (net (code "7") (name "Net-(LED4-DOUT)") (class "Default")
      (node (ref "LED4") (pin "2") (pinfunction "DOUT_2") (pintype "passive"))
      (node (ref "LED5") (pin "4") (pinfunction "DIN_4") (pintype "passive"))
    )
    (net (code "8") (name "Net-(LED5-DOUT)") (class "Default")
      (node (ref "LED5") (pin "2") (pinfunction "DOUT_2") (pintype "passive"))
      (node (ref "LED6") (pin "4") (pinfunction "DIN_4") (pintype "passive"))
    )
    (net (code "9") (name "Net-(LED6-DOUT)") (class "Default")
      (node (ref "LED6") (pin "2") (pinfunction "DOUT_2") (pintype "passive"))
      (node (ref "LED7") (pin "4") (pinfunction "DIN_4") (pintype "passive"))
    )
    (net (code "10") (name "Net-(LED7-DOUT)") (class "Default")
      (node (ref "LED7") (pin "2") (pinfunction "DOUT_2") (pintype "passive"))
      (node (ref "LED8") (pin "4") (pinfunction "DIN_4") (pintype "passive"))
    )
    (net (code "11") (name "Net-(LED8-DOUT)") (class "Default")
      (node (ref "LED8") (pin "2") (pinfunction "DOUT_2") (pintype "passive"))
      (node (ref "LED9") (pin "4") (pinfunction "DIN_4") (pintype "passive"))
    )
    (net (code "12") (name "Net-(LED10-DIN)") (class "Default")
      (node (ref "LED10") (pin "4") (pinfunction "DIN_4") (pintype "passive"))
      (node (ref "LED9") (pin "2") (pinfunction "DOUT_2") (pintype "passive"))
    )
    (net (code "13") (name "Net-(LED10-DOUT)") (class "Default")
      (node (ref "LED10") (pin "2") (pinfunction "DOUT_2") (pintype "passive"))
      (node (ref "LED11") (pin "4") (pinfunction "DIN_4") (pintype "passive"))
    )
    (net (code "14") (name "Net-(LED11-DOUT)") (class "Default")
      (node (ref "LED11") (pin "2") (pinfunction "DOUT_2") (pintype "passive"))
      (node (ref "LED12") (pin "4") (pinfunction "DIN_4") (pintype "passive"))
    )
    (net (code "15") (name "Net-(LED12-DOUT)") (class "Default")
      (node (ref "LED12") (pin "2") (pinfunction "DOUT_2") (pintype "passive"))
      (node (ref "LED13") (pin "4") (pinfunction "DIN_4") (pintype "passive"))
    )
    (net (code "16") (name "Net-(LED13-DOUT)") (class "Default")
      (node (ref "LED13") (pin "2") (pinfunction "DOUT_2") (pintype "passive"))
      (node (ref "LED14") (pin "4") (pinfunction "DIN_4") (pintype "passive"))
    )
    (net (code "17") (name "Net-(LED14-DOUT)") (class "Default")
      (node (ref "LED14") (pin "2") (pinfunction "DOUT_2") (pintype "passive"))
      (node (ref "LED15") (pin "4") (pinfunction "DIN_4") (pintype "passive"))
    )
    (net (code "18") (name "Net-(LED15-DOUT)") (class "Default")
      (node (ref "LED15") (pin "2") (pinfunction "DOUT_2") (pintype "passive"))
      (node (ref "LED16") (pin "4") (pinfunction "DIN_4") (pintype "passive"))
    )
    (net (code "19") (name "Net-(LED16-DOUT)") (class "Default")
      (node (ref "LED16") (pin "2") (pinfunction "DOUT_2") (pintype "passive"))
      (node (ref "LED17") (pin "4") (pinfunction "DIN_4") (pintype "passive"))
    )
    (net (code "20") (name "Net-(LED17-DOUT)") (class "Default")
      (node (ref "LED17") (pin "2") (pinfunction "DOUT_2") (pintype "passive"))
      (node (ref "LED18") (pin "4") (pinfunction "DIN_4") (pintype "passive"))
    )
    (net (code "21") (name "Net-(LED18-DOUT)") (class "Default")
      (node (ref "LED18") (pin "2") (pinfunction "DOUT_2") (pintype "passive"))
      (node (ref "LED19") (pin "4") (pinfunction "DIN_4") (pintype "passive"))
    )
    (net (code "22") (name "Net-(LED19-DOUT)") (class "Default")
      (node (ref "LED19") (pin "2") (pinfunction "DOUT_2") (pintype "passive"))
      (node (ref "LED20") (pin "4") (pinfunction "DIN_4") (pintype "passive"))
    )
    (net (code "23") (name "Net-(LED20-DOUT)") (class "Default")
      (node (ref "LED20") (pin "2") (pinfunction "DOUT_2") (pintype "passive"))
      (node (ref "LED21") (pin "4") (pinfunction "DIN_4") (pintype "passive"))
    )
    (net (code "24") (name "Net-(LED21-DOUT)") (class "Default")
      (node (ref "LED21") (pin "2") (pinfunction "DOUT_2") (pintype "passive"))
      (node (ref "LED22") (pin "4") (pinfunction "DIN_4") (pintype "passive"))
    )
    (net (code "25") (name "Net-(LED22-DOUT)") (class "Default")
      (node (ref "LED22") (pin "2") (pinfunction "DOUT_2") (pintype "passive"))
      (node (ref "LED23") (pin "4") (pinfunction "DIN_4") (pintype "passive"))
    )
    (net (code "26") (name "Net-(LED23-DOUT)") (class "Default")
      (node (ref "LED23") (pin "2") (pinfunction "DOUT_2") (pintype "passive"))
      (node (ref "LED24") (pin "4") (pinfunction "DIN_4") (pintype "passive"))
    )
    (net (code "27") (name "Net-(LED24-DOUT)") (class "Default")
      (node (ref "LED24") (pin "2") (pinfunction "DOUT_2") (pintype "passive"))
      (node (ref "LED25") (pin "4") (pinfunction "DIN_4") (pintype "passive"))
    )
    (net (code "28") (name "Net-(LED25-DOUT)") (class "Default")
      (node (ref "LED25") (pin "2") (pinfunction "DOUT_2") (pintype "passive"))
      (node (ref "LED26") (pin "4") (pinfunction "DIN_4") (pintype "passive"))
    )
    (net (code "29") (name "Net-(LED26-DOUT)") (class "Default")
      (node (ref "LED26") (pin "2") (pinfunction "DOUT_2") (pintype "passive"))
      (node (ref "LED27") (pin "4") (pinfunction "DIN_4") (pintype "passive"))
    )
    (net (code "30") (name "Net-(LED27-DOUT)") (class "Default")
      (node (ref "LED27") (pin "2") (pinfunction "DOUT_2") (pintype "passive"))
      (node (ref "LED28") (pin "4") (pinfunction "DIN_4") (pintype "passive"))
    )
    (net (code "31") (name "Net-(LED28-DOUT)") (class "Default")
      (node (ref "LED28") (pin "2") (pinfunction "DOUT_2") (pintype "passive"))
      (node (ref "LED29") (pin "4") (pinfunction "DIN_4") (pintype "passive"))
    )
    (net (code "32") (name "Net-(LED29-DOUT)") (class "Default")
      (node (ref "LED29") (pin "2") (pinfunction "DOUT_2") (pintype "passive"))
      (node (ref "LED30") (pin "4") (pinfunction "DIN_4") (pintype "passive"))
    )
    (net (code "33") (name "Net-(LED30-DOUT)") (class "Default")
      (node (ref "LED30") (pin "2") (pinfunction "DOUT_2") (pintype "passive"))
      (node (ref "LED31") (pin "4") (pinfunction "DIN_4") (pintype "passive"))
    )
    (net (code "34") (name "Net-(LED31-DOUT)") (class "Default")
      (node (ref "LED31") (pin "2") (pinfunction "DOUT_2") (pintype "passive"))
      (node (ref "LED32") (pin "4") (pinfunction "DIN_4") (pintype "passive"))
    )
    (net (code "35") (name "Net-(LED32-DOUT)") (class "Default")
      (node (ref "LED32") (pin "2") (pinfunction "DOUT_2") (pintype "passive"))
      (node (ref "LED33") (pin "4") (pinfunction "DIN_4") (pintype "passive"))
    )
    (net (code "36") (name "Net-(LED33-DOUT)") (class "Default")
      (node (ref "LED33") (pin "2") (pinfunction "DOUT_2") (pintype "passive"))
      (node (ref "LED34") (pin "4") (pinfunction "DIN_4") (pintype "passive"))
    )
    (net (code "37") (name "Net-(LED34-DOUT)") (class "Default")
      (node (ref "LED34") (pin "2") (pinfunction "DOUT_2") (pintype "passive"))
      (node (ref "LED35") (pin "4") (pinfunction "DIN_4") (pintype "passive"))
    )
    (net (code "38") (name "Net-(LED35-DOUT)") (class "Default")
      (node (ref "LED35") (pin "2") (pinfunction "DOUT_2") (pintype "passive"))
      (node (ref "LED36") (pin "4") (pinfunction "DIN_4") (pintype "passive"))
    )
    (net (code "39") (name "Net-(LED36-DOUT)") (class "Default")
      (node (ref "LED36") (pin "2") (pinfunction "DOUT_2") (pintype "passive"))
      (node (ref "LED37") (pin "4") (pinfunction "DIN_4") (pintype "passive"))
    )
    (net (code "40") (name "Net-(LED37-DOUT)") (class "Default")
      (node (ref "LED37") (pin "2") (pinfunction "DOUT_2") (pintype "passive"))
      (node (ref "LED38") (pin "4") (pinfunction "DIN_4") (pintype "passive"))
    )
    (net (code "41") (name "Net-(LED38-DOUT)") (class "Default")
      (node (ref "LED38") (pin "2") (pinfunction "DOUT_2") (pintype "passive"))
      (node (ref "LED39") (pin "4") (pinfunction "DIN_4") (pintype "passive"))
    )
    (net (code "42") (name "Net-(LED39-DOUT)") (class "Default")
      (node (ref "LED39") (pin "2") (pinfunction "DOUT_2") (pintype "passive"))
      (node (ref "LED40") (pin "4") (pinfunction "DIN_4") (pintype "passive"))
    )
    (net (code "43") (name "Net-(LED40-DOUT)") (class "Default")
      (node (ref "LED40") (pin "2") (pinfunction "DOUT_2") (pintype "passive"))
      (node (ref "LED41") (pin "4") (pinfunction "DIN_4") (pintype "passive"))
    )
    (net (code "44") (name "Net-(LED41-DOUT)") (class "Default")
      (node (ref "LED41") (pin "2") (pinfunction "DOUT_2") (pintype "passive"))
      (node (ref "LED42") (pin "4") (pinfunction "DIN_4") (pintype "passive"))
    )
    (net (code "45") (name "Net-(LED42-DOUT)") (class "Default")
      (node (ref "LED42") (pin "2") (pinfunction "DOUT_2") (pintype "passive"))
      (node (ref "LED43") (pin "4") (pinfunction "DIN_4") (pintype "passive"))
    )
    (net (code "46") (name "Net-(LED43-DOUT)") (class "Default")
      (node (ref "LED43") (pin "2") (pinfunction "DOUT_2") (pintype "passive"))
      (node (ref "LED44") (pin "4") (pinfunction "DIN_4") (pintype "passive"))
    )
    (net (code "47") (name "Net-(LED44-DOUT)") (class "Default")
      (node (ref "LED44") (pin "2") (pinfunction "DOUT_2") (pintype "passive"))
      (node (ref "LED45") (pin "4") (pinfunction "DIN_4") (pintype "passive"))
    )
    (net (code "48") (name "Net-(LED45-DOUT)") (class "Default")
      (node (ref "LED45") (pin "2") (pinfunction "DOUT_2") (pintype "passive"))
      (node (ref "LED46") (pin "4") (pinfunction "DIN_4") (pintype "passive"))
    )
    (net (code "49") (name "Net-(LED46-DOUT)") (class "Default")
      (node (ref "LED46") (pin "2") (pinfunction "DOUT_2") (pintype "passive"))
      (node (ref "LED47") (pin "4") (pinfunction "DIN_4") (pintype "passive"))
    )
    (net (code "50") (name "Net-(LED47-DOUT)") (class "Default")
      (node (ref "LED47") (pin "2") (pinfunction "DOUT_2") (pintype "passive"))
      (node (ref "LED48") (pin "4") (pinfunction "DIN_4") (pintype "passive"))
    )
    (net (code "51") (name "Net-(LED48-DOUT)") (class "Default")
      (node (ref "LED48") (pin "2") (pinfunction "DOUT_2") (pintype "passive"))
      (node (ref "LED49") (pin "4") (pinfunction "DIN_4") (pintype "passive"))
    )
    (net (code "52") (name "Net-(LED49-DOUT)") (class "Default")
      (node (ref "LED49") (pin "2") (pinfunction "DOUT_2") (pintype "passive"))
      (node (ref "LED50") (pin "4") (pinfunction "DIN_4") (pintype "passive"))
    )
    (net (code "53") (name "Net-(LED50-DOUT)") (class "Default")
      (node (ref "LED50") (pin "2") (pinfunction "DOUT_2") (pintype "passive"))
      (node (ref "LED51") (pin "4") (pinfunction "DIN_4") (pintype "passive"))
    )
    (net (code "54") (name "Net-(LED51-DOUT)") (class "Default")
      (node (ref "LED51") (pin "2") (pinfunction "DOUT_2") (pintype "passive"))
      (node (ref "LED52") (pin "4") (pinfunction "DIN_4") (pintype "passive"))
    )
    (net (code "55") (name "Net-(LED52-DOUT)") (class "Default")
      (node (ref "LED52") (pin "2") (pinfunction "DOUT_2") (pintype "passive"))
      (node (ref "LED53") (pin "4") (pinfunction "DIN_4") (pintype "passive"))
    )
    (net (code "56") (name "Net-(LED53-DOUT)") (class "Default")
      (node (ref "LED53") (pin "2") (pinfunction "DOUT_2") (pintype "passive"))
      (node (ref "LED54") (pin "4") (pinfunction "DIN_4") (pintype "passive"))
    )
    (net (code "57") (name "Net-(LED54-DOUT)") (class "Default")
      (node (ref "LED54") (pin "2") (pinfunction "DOUT_2") (pintype "passive"))
      (node (ref "LED55") (pin "4") (pinfunction "DIN_4") (pintype "passive"))
    )
    (net (code "58") (name "Net-(LED55-DOUT)") (class "Default")
      (node (ref "LED55") (pin "2") (pinfunction "DOUT_2") (pintype "passive"))
      (node (ref "LED56") (pin "4") (pinfunction "DIN_4") (pintype "passive"))
    )
    (net (code "59") (name "Net-(LED56-DOUT)") (class "Default")
      (node (ref "LED56") (pin "2") (pinfunction "DOUT_2") (pintype "passive"))
      (node (ref "LED57") (pin "4") (pinfunction "DIN_4") (pintype "passive"))
    )
    (net (code "60") (name "Net-(LED57-DOUT)") (class "Default")
      (node (ref "LED57") (pin "2") (pinfunction "DOUT_2") (pintype "passive"))
      (node (ref "LED58") (pin "4") (pinfunction "DIN_4") (pintype "passive"))
    )
    (net (code "61") (name "Net-(LED58-DOUT)") (class "Default")
      (node (ref "LED58") (pin "2") (pinfunction "DOUT_2") (pintype "passive"))
      (node (ref "LED59") (pin "4") (pinfunction "DIN_4") (pintype "passive"))
    )
    (net (code "62") (name "Net-(LED59-DOUT)") (class "Default")
      (node (ref "LED59") (pin "2") (pinfunction "DOUT_2") (pintype "passive"))
      (node (ref "LED60") (pin "4") (pinfunction "DIN_4") (pintype "passive"))
    )
    (net (code "63") (name "Net-(LED60-DOUT)") (class "Default")
      (node (ref "LED60") (pin "2") (pinfunction "DOUT_2") (pintype "passive"))
      (node (ref "LED61") (pin "4") (pinfunction "DIN_4") (pintype "passive"))
    )
    (net (code "64") (name "Net-(LED61-DOUT)") (class "Default")
      (node (ref "LED61") (pin "2") (pinfunction "DOUT_2") (pintype "passive"))
      (node (ref "LED62") (pin "4") (pinfunction "DIN_4") (pintype "passive"))
    )
    (net (code "65") (name "Net-(LED62-DOUT)") (class "Default")
      (node (ref "LED62") (pin "2") (pinfunction "DOUT_2") (pintype "passive"))
      (node (ref "LED63") (pin "4") (pinfunction "DIN_4") (pintype "passive"))
    )
    (net (code "66") (name "Net-(LED63-DOUT)") (class "Default")
      (node (ref "LED63") (pin "2") (pinfunction "DOUT_2") (pintype "passive"))
      (node (ref "LED64") (pin "4") (pinfunction "DIN_4") (pintype "passive"))
    )
    (net (code "67") (name "Net-(LED64-DOUT)") (class "Default")
      (node (ref "LED64") (pin "2") (pinfunction "DOUT_2") (pintype "passive"))
      (node (ref "LED65") (pin "4") (pinfunction "DIN_4") (pintype "passive"))
    )
    (net (code "68") (name "Net-(LED65-DOUT)") (class "Default")
      (node (ref "LED65") (pin "2") (pinfunction "DOUT_2") (pintype "passive"))
      (node (ref "LED66") (pin "4") (pinfunction "DIN_4") (pintype "passive"))
    )
    (net (code "69") (name "Net-(LED66-DOUT)") (class "Default")
      (node (ref "LED66") (pin "2") (pinfunction "DOUT_2") (pintype "passive"))
      (node (ref "LED67") (pin "4") (pinfunction "DIN_4") (pintype "passive"))
    )
    (net (code "70") (name "Net-(LED67-DOUT)") (class "Default")
      (node (ref "LED67") (pin "2") (pinfunction "DOUT_2") (pintype "passive"))
      (node (ref "LED68") (pin "4") (pinfunction "DIN_4") (pintype "passive"))
    )
    (net (code "71") (name "Net-(LED68-DOUT)") (class "Default")
      (node (ref "LED68") (pin "2") (pinfunction "DOUT_2") (pintype "passive"))
      (node (ref "LED69") (pin "4") (pinfunction "DIN_4") (pintype "passive"))
    )
    (net (code "72") (name "Net-(LED69-DOUT)") (class "Default")
      (node (ref "LED69") (pin "2") (pinfunction "DOUT_2") (pintype "passive"))
      (node (ref "LED70") (pin "4") (pinfunction "DIN_4") (pintype "passive"))
    )
    (net (code "73") (name "Net-(LED70-DOUT)") (class "Default")
      (node (ref "LED70") (pin "2") (pinfunction "DOUT_2") (pintype "passive"))
      (node (ref "LED71") (pin "4") (pinfunction "DIN_4") (pintype "passive"))
    )
    (net (code "74") (name "Net-(LED71-DOUT)") (class "Default")
      (node (ref "LED71") (pin "2") (pinfunction "DOUT_2") (pintype "passive"))
      (node (ref "LED72") (pin "4") (pinfunction "DIN_4") (pintype "passive"))
    )
    (net (code "75") (name "Net-(LED72-DOUT)") (class "Default")
      (node (ref "LED72") (pin "2") (pinfunction "DOUT_2") (pintype "passive"))
      (node (ref "LED73") (pin "4") (pinfunction "DIN_4") (pintype "passive"))
    )
    (net (code "76") (name "Net-(LED73-DOUT)") (class "Default")
      (node (ref "LED73") (pin "2") (pinfunction "DOUT_2") (pintype "passive"))
      (node (ref "LED74") (pin "4") (pinfunction "DIN_4") (pintype "passive"))
    )
    (net (code "77") (name "Net-(LED74-DOUT)") (class "Default")
      (node (ref "LED74") (pin "2") (pinfunction "DOUT_2") (pintype "passive"))
      (node (ref "LED75") (pin "4") (pinfunction "DIN_4") (pintype "passive"))
    )
    (net (code "78") (name "Net-(LED75-DOUT)") (class "Default")
      (node (ref "LED75") (pin "2") (pinfunction "DOUT_2") (pintype "passive"))
      (node (ref "LED76") (pin "4") (pinfunction "DIN_4") (pintype "passive"))
    )
    (net (code "79") (name "Net-(LED76-DOUT)") (class "Default")
      (node (ref "LED76") (pin "2") (pinfunction "DOUT_2") (pintype "passive"))
      (node (ref "LED77") (pin "4") (pinfunction "DIN_4") (pintype "passive"))
    )
    (net (code "80") (name "Net-(LED77-DOUT)") (class "Default")
      (node (ref "LED77") (pin "2") (pinfunction "DOUT_2") (pintype "passive"))
      (node (ref "LED78") (pin "4") (pinfunction "DIN_4") (pintype "passive"))
    )
    (net (code "81") (name "Net-(LED78-DOUT)") (class "Default")
      (node (ref "LED78") (pin "2") (pinfunction "DOUT_2") (pintype "passive"))
      (node (ref "LED79") (pin "4") (pinfunction "DIN_4") (pintype "passive"))
    )
    (net (code "82") (name "Net-(LED79-DOUT)") (class "Default")
      (node (ref "LED79") (pin "2") (pinfunction "DOUT_2") (pintype "passive"))
      (node (ref "LED80") (pin "4") (pinfunction "DIN_4") (pintype "passive"))
    )
    (net (code "83") (name "Net-(LED80-DOUT)") (class "Default")
      (node (ref "LED80") (pin "2") (pinfunction "DOUT_2") (pintype "passive"))
      (node (ref "LED81") (pin "4") (pinfunction "DIN_4") (pintype "passive"))
    )
    (net (code "84") (name "Net-(LED81-DOUT)") (class "Default")
      (node (ref "LED81") (pin "2") (pinfunction "DOUT_2") (pintype "passive"))
      (node (ref "LED82") (pin "4") (pinfunction "DIN_4") (pintype "passive"))
    )
    (net (code "85") (name "Net-(LED82-DOUT)") (class "Default")
      (node (ref "LED82") (pin "2") (pinfunction "DOUT_2") (pintype "passive"))
      (node (ref "LED83") (pin "4") (pinfunction "DIN_4") (pintype "passive"))
    )
    (net (code "86") (name "Net-(LED83-DOUT)") (class "Default")
      (node (ref "LED83") (pin "2") (pinfunction "DOUT_2") (pintype "passive"))
      (node (ref "LED84") (pin "4") (pinfunction "DIN_4") (pintype "passive"))
    )
    (net (code "87") (name "Net-(LED84-DOUT)") (class "Default")
      (node (ref "LED84") (pin "2") (pinfunction "DOUT_2") (pintype "passive"))
      (node (ref "LED85") (pin "4") (pinfunction "DIN_4") (pintype "passive"))
    )
    (net (code "88") (name "Net-(LED85-DOUT)") (class "Default")
      (node (ref "LED85") (pin "2") (pinfunction "DOUT_2") (pintype "passive"))
      (node (ref "LED86") (pin "4") (pinfunction "DIN_4") (pintype "passive"))
    )
    (net (code "89") (name "Net-(LED86-DOUT)") (class "Default")
      (node (ref "LED86") (pin "2") (pinfunction "DOUT_2") (pintype "passive"))
      (node (ref "LED87") (pin "4") (pinfunction "DIN_4") (pintype "passive"))
    )
    (net (code "90") (name "Net-(LED87-DOUT)") (class "Default")
      (node (ref "LED87") (pin "2") (pinfunction "DOUT_2") (pintype "passive"))
      (node (ref "LED88") (pin "4") (pinfunction "DIN_4") (pintype "passive"))
    )
    (net (code "91") (name "Net-(LED88-DOUT)") (class "Default")
      (node (ref "LED88") (pin "2") (pinfunction "DOUT_2") (pintype "passive"))
      (node (ref "LED89") (pin "4") (pinfunction "DIN_4") (pintype "passive"))
    )
    (net (code "92") (name "Net-(LED89-DOUT)") (class "Default")
      (node (ref "LED89") (pin "2") (pinfunction "DOUT_2") (pintype "passive"))
      (node (ref "LED90") (pin "4") (pinfunction "DIN_4") (pintype "passive"))
    )
    (net (code "93") (name "Net-(LED90-DOUT)") (class "Default")
      (node (ref "LED90") (pin "2") (pinfunction "DOUT_2") (pintype "passive"))
      (node (ref "LED91") (pin "4") (pinfunction "DIN_4") (pintype "passive"))
    )
    (net (code "94") (name "Net-(LED91-DOUT)") (class "Default")
      (node (ref "LED91") (pin "2") (pinfunction "DOUT_2") (pintype "passive"))
      (node (ref "LED92") (pin "4") (pinfunction "DIN_4") (pintype "passive"))
    )
    (net (code "95") (name "Net-(LED92-DOUT)") (class "Default")
      (node (ref "LED92") (pin "2") (pinfunction "DOUT_2") (pintype "passive"))
      (node (ref "LED93") (pin "4") (pinfunction "DIN_4") (pintype "passive"))
    )
    (net (code "96") (name "Net-(LED93-DOUT)") (class "Default")
      (node (ref "LED93") (pin "2") (pinfunction "DOUT_2") (pintype "passive"))
      (node (ref "LED94") (pin "4") (pinfunction "DIN_4") (pintype "passive"))
    )
    (net (code "97") (name "Net-(LED94-DOUT)") (class "Default")
      (node (ref "LED94") (pin "2") (pinfunction "DOUT_2") (pintype "passive"))
      (node (ref "LED95") (pin "4") (pinfunction "DIN_4") (pintype "passive"))
    )
    (net (code "98") (name "Net-(LED95-DOUT)") (class "Default")
      (node (ref "LED95") (pin "2") (pinfunction "DOUT_2") (pintype "passive"))
      (node (ref "LED96") (pin "4") (pinfunction "DIN_4") (pintype "passive"))
    )
    (net (code "99") (name "Net-(LED96-DOUT)") (class "Default")
      (node (ref "LED96") (pin "2") (pinfunction "DOUT_2") (pintype "passive"))
      (node (ref "LED97") (pin "4") (pinfunction "DIN_4") (pintype "passive"))
    )
    (net (code "100") (name "Net-(LED97-DOUT)") (class "Default")
      (node (ref "LED97") (pin "2") (pinfunction "DOUT_2") (pintype "passive"))
      (node (ref "LED98") (pin "4") (pinfunction "DIN_4") (pintype "passive"))
    )
    (net (code "101") (name "Net-(LED98-DOUT)") (class "Default")
      (node (ref "LED98") (pin "2") (pinfunction "DOUT_2") (pintype "passive"))
      (node (ref "LED99") (pin "4") (pinfunction "DIN_4") (pintype "passive"))
    )
    (net (code "102") (name "Net-(LED100-DIN)") (class "Default")
      (node (ref "LED100") (pin "4") (pinfunction "DIN_4") (pintype "passive"))
      (node (ref "LED99") (pin "2") (pinfunction "DOUT_2") (pintype "passive"))
    )
    (net (code "103") (name "Net-(LED100-DOUT)") (class "Default")
      (node (ref "LED100") (pin "2") (pinfunction "DOUT_2") (pintype "passive"))
      (node (ref "LED101") (pin "4") (pinfunction "DIN_4") (pintype "passive"))
    )
    (net (code "104") (name "Net-(LED101-DOUT)") (class "Default")
      (node (ref "LED101") (pin "2") (pinfunction "DOUT_2") (pintype "passive"))
      (node (ref "LED102") (pin "4") (pinfunction "DIN_4") (pintype "passive"))
    )
    (net (code "105") (name "Net-(LED102-DOUT)") (class "Default")
      (node (ref "LED102") (pin "2") (pinfunction "DOUT_2") (pintype "passive"))
      (node (ref "LED103") (pin "4") (pinfunction "DIN_4") (pintype "passive"))
    )
    (net (code "106") (name "Net-(LED103-DOUT)") (class "Default")
      (node (ref "LED103") (pin "2") (pinfunction "DOUT_2") (pintype "passive"))
      (node (ref "LED104") (pin "4") (pinfunction "DIN_4") (pintype "passive"))
    )
    (net (code "107") (name "Net-(LED104-DOUT)") (class "Default")
      (node (ref "LED104") (pin "2") (pinfunction "DOUT_2") (pintype "passive"))
      (node (ref "LED105") (pin "4") (pinfunction "DIN_4") (pintype "passive"))
    )
    (net (code "108") (name "Net-(LED105-DOUT)") (class "Default")
      (node (ref "LED105") (pin "2") (pinfunction "DOUT_2") (pintype "passive"))
      (node (ref "LED106") (pin "4") (pinfunction "DIN_4") (pintype "passive"))
    )
    (net (code "109") (name "Net-(LED106-DOUT)") (class "Default")
      (node (ref "LED106") (pin "2") (pinfunction "DOUT_2") (pintype "passive"))
      (node (ref "LED107") (pin "4") (pinfunction "DIN_4") (pintype "passive"))
    )
    (net (code "110") (name "Net-(LED107-DOUT)") (class "Default")
      (node (ref "LED107") (pin "2") (pinfunction "DOUT_2") (pintype "passive"))
      (node (ref "LED108") (pin "4") (pinfunction "DIN_4") (pintype "passive"))
    )
    (net (code "111") (name "Net-(LED108-DOUT)") (class "Default")
      (node (ref "LED108") (pin "2") (pinfunction "DOUT_2") (pintype "passive"))
      (node (ref "LED109") (pin "4") (pinfunction "DIN_4") (pintype "passive"))
    )
    (net (code "112") (name "Net-(LED109-DOUT)") (class "Default")
      (node (ref "LED109") (pin "2") (pinfunction "DOUT_2") (pintype "passive"))
      (node (ref "LED110") (pin "4") (pinfunction "DIN_4") (pintype "passive"))
    )
    (net (code "113") (name "Net-(LED110-DOUT)") (class "Default")
      (node (ref "LED110") (pin "2") (pinfunction "DOUT_2") (pintype "passive"))
      (node (ref "LED111") (pin "4") (pinfunction "DIN_4") (pintype "passive"))
    )
    (net (code "114") (name "Net-(LED111-DOUT)") (class "Default")
      (node (ref "LED111") (pin "2") (pinfunction "DOUT_2") (pintype "passive"))
      (node (ref "LED112") (pin "4") (pinfunction "DIN_4") (pintype "passive"))
    )
    (net (code "115") (name "Net-(LED112-DOUT)") (class "Default")
      (node (ref "LED112") (pin "2") (pinfunction "DOUT_2") (pintype "passive"))
      (node (ref "LED113") (pin "4") (pinfunction "DIN_4") (pintype "passive"))
    )
    (net (code "116") (name "Net-(LED113-DOUT)") (class "Default")
      (node (ref "LED113") (pin "2") (pinfunction "DOUT_2") (pintype "passive"))
      (node (ref "LED114") (pin "4") (pinfunction "DIN_4") (pintype "passive"))
    )
    (net (code "117") (name "Net-(LED114-DOUT)") (class "Default")
      (node (ref "LED114") (pin "2") (pinfunction "DOUT_2") (pintype "passive"))
      (node (ref "LED115") (pin "4") (pinfunction "DIN_4") (pintype "passive"))
    )
    (net (code "118") (name "Net-(LED115-DOUT)") (class "Default")
      (node (ref "LED115") (pin "2") (pinfunction "DOUT_2") (pintype "passive"))
      (node (ref "LED116") (pin "4") (pinfunction "DIN_4") (pintype "passive"))
    )
    (net (code "119") (name "Net-(LED116-DOUT)") (class "Default")
      (node (ref "LED116") (pin "2") (pinfunction "DOUT_2") (pintype "passive"))
      (node (ref "LED117") (pin "4") (pinfunction "DIN_4") (pintype "passive"))
    )
    (net (code "120") (name "Net-(LED117-DOUT)") (class "Default")
      (node (ref "LED117") (pin "2") (pinfunction "DOUT_2") (pintype "passive"))
      (node (ref "LED118") (pin "4") (pinfunction "DIN_4") (pintype "passive"))
    )
    (net (code "121") (name "Net-(LED118-DOUT)") (class "Default")
      (node (ref "LED118") (pin "2") (pinfunction "DOUT_2") (pintype "passive"))
      (node (ref "LED119") (pin "4") (pinfunction "DIN_4") (pintype "passive"))
    )
    (net (code "122") (name "Net-(LED119-DOUT)") (class "Default")
      (node (ref "LED119") (pin "2") (pinfunction "DOUT_2") (pintype "passive"))
      (node (ref "LED120") (pin "4") (pinfunction "DIN_4") (pintype "passive"))
    )
    (net (code "123") (name "Net-(LED120-DOUT)") (class "Default")
      (node (ref "LED120") (pin "2") (pinfunction "DOUT_2") (pintype "passive"))
      (node (ref "LED121") (pin "4") (pinfunction "DIN_4") (pintype "passive"))
    )
    (net (code "124") (name "Net-(LED121-DOUT)") (class "Default")
      (node (ref "LED121") (pin "2") (pinfunction "DOUT_2") (pintype "passive"))
      (node (ref "LED122") (pin "4") (pinfunction "DIN_4") (pintype "passive"))
    )
    (net (code "125") (name "Net-(LED122-DOUT)") (class "Default")
      (node (ref "LED122") (pin "2") (pinfunction "DOUT_2") (pintype "passive"))
      (node (ref "LED123") (pin "4") (pinfunction "DIN_4") (pintype "passive"))
    )
    (net (code "126") (name "Net-(LED123-DOUT)") (class "Default")
      (node (ref "LED123") (pin "2") (pinfunction "DOUT_2") (pintype "passive"))
      (node (ref "LED124") (pin "4") (pinfunction "DIN_4") (pintype "passive"))
    )
    (net (code "127") (name "Net-(LED124-DOUT)") (class "Default")
      (node (ref "LED124") (pin "2") (pinfunction "DOUT_2") (pintype "passive"))
      (node (ref "LED125") (pin "4") (pinfunction "DIN_4") (pintype "passive"))
    )
    (net (code "128") (name "Net-(LED125-DOUT)") (class "Default")
      (node (ref "LED125") (pin "2") (pinfunction "DOUT_2") (pintype "passive"))
      (node (ref "LED126") (pin "4") (pinfunction "DIN_4") (pintype "passive"))
    )
    (net (code "129") (name "Net-(LED126-DOUT)") (class "Default")
      (node (ref "LED126") (pin "2") (pinfunction "DOUT_2") (pintype "passive"))
      (node (ref "LED127") (pin "4") (pinfunction "DIN_4") (pintype "passive"))
    )
    (net (code "130") (name "Net-(LED127-DOUT)") (class "Default")
      (node (ref "LED127") (pin "2") (pinfunction "DOUT_2") (pintype "passive"))
      (node (ref "LED128") (pin "4") (pinfunction "DIN_4") (pintype "passive"))
    )
    (net (code "131") (name "Net-(LED128-DOUT)") (class "Default")
      (node (ref "LED128") (pin "2") (pinfunction "DOUT_2") (pintype "passive"))
      (node (ref "LED129") (pin "4") (pinfunction "DIN_4") (pintype "passive"))
    )
    (net (code "132") (name "unconnected-(LED129-DOUT-Pad2)") (class "Default")
      (node (ref "LED129") (pin "2") (pinfunction "DOUT_2") (pintype "passive"))
    )
  )
)
